# mk312_smt_main_V2.net
KiCad netlist of a schematic drawn in EAGLE
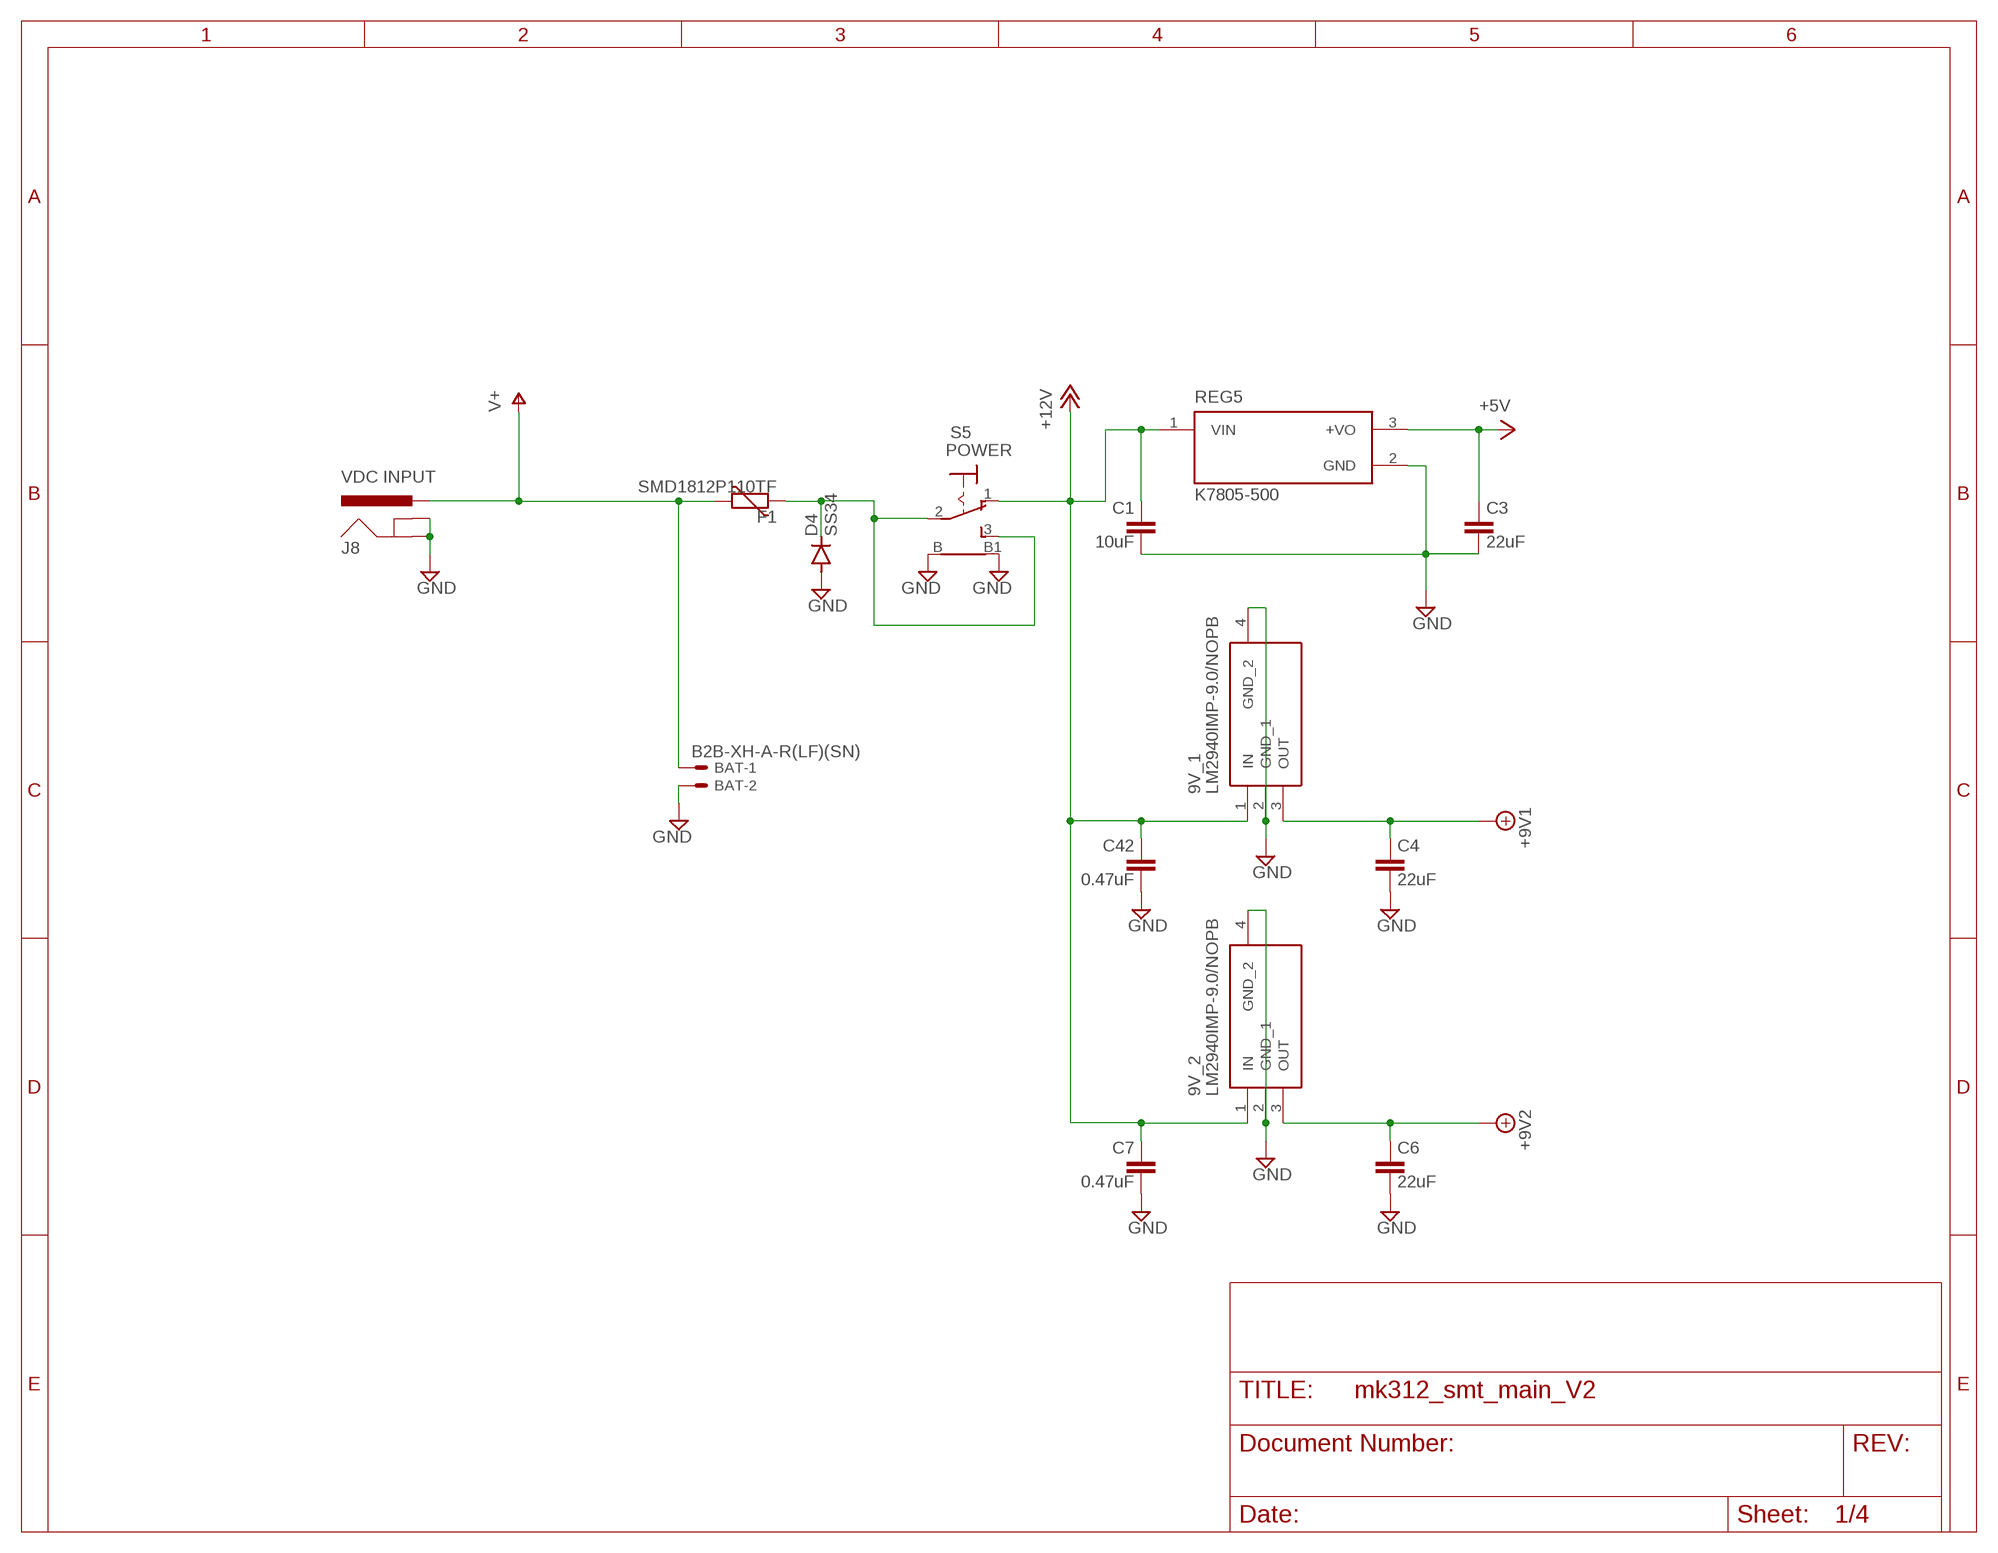
[diagram p0: schematic, sheet 1]
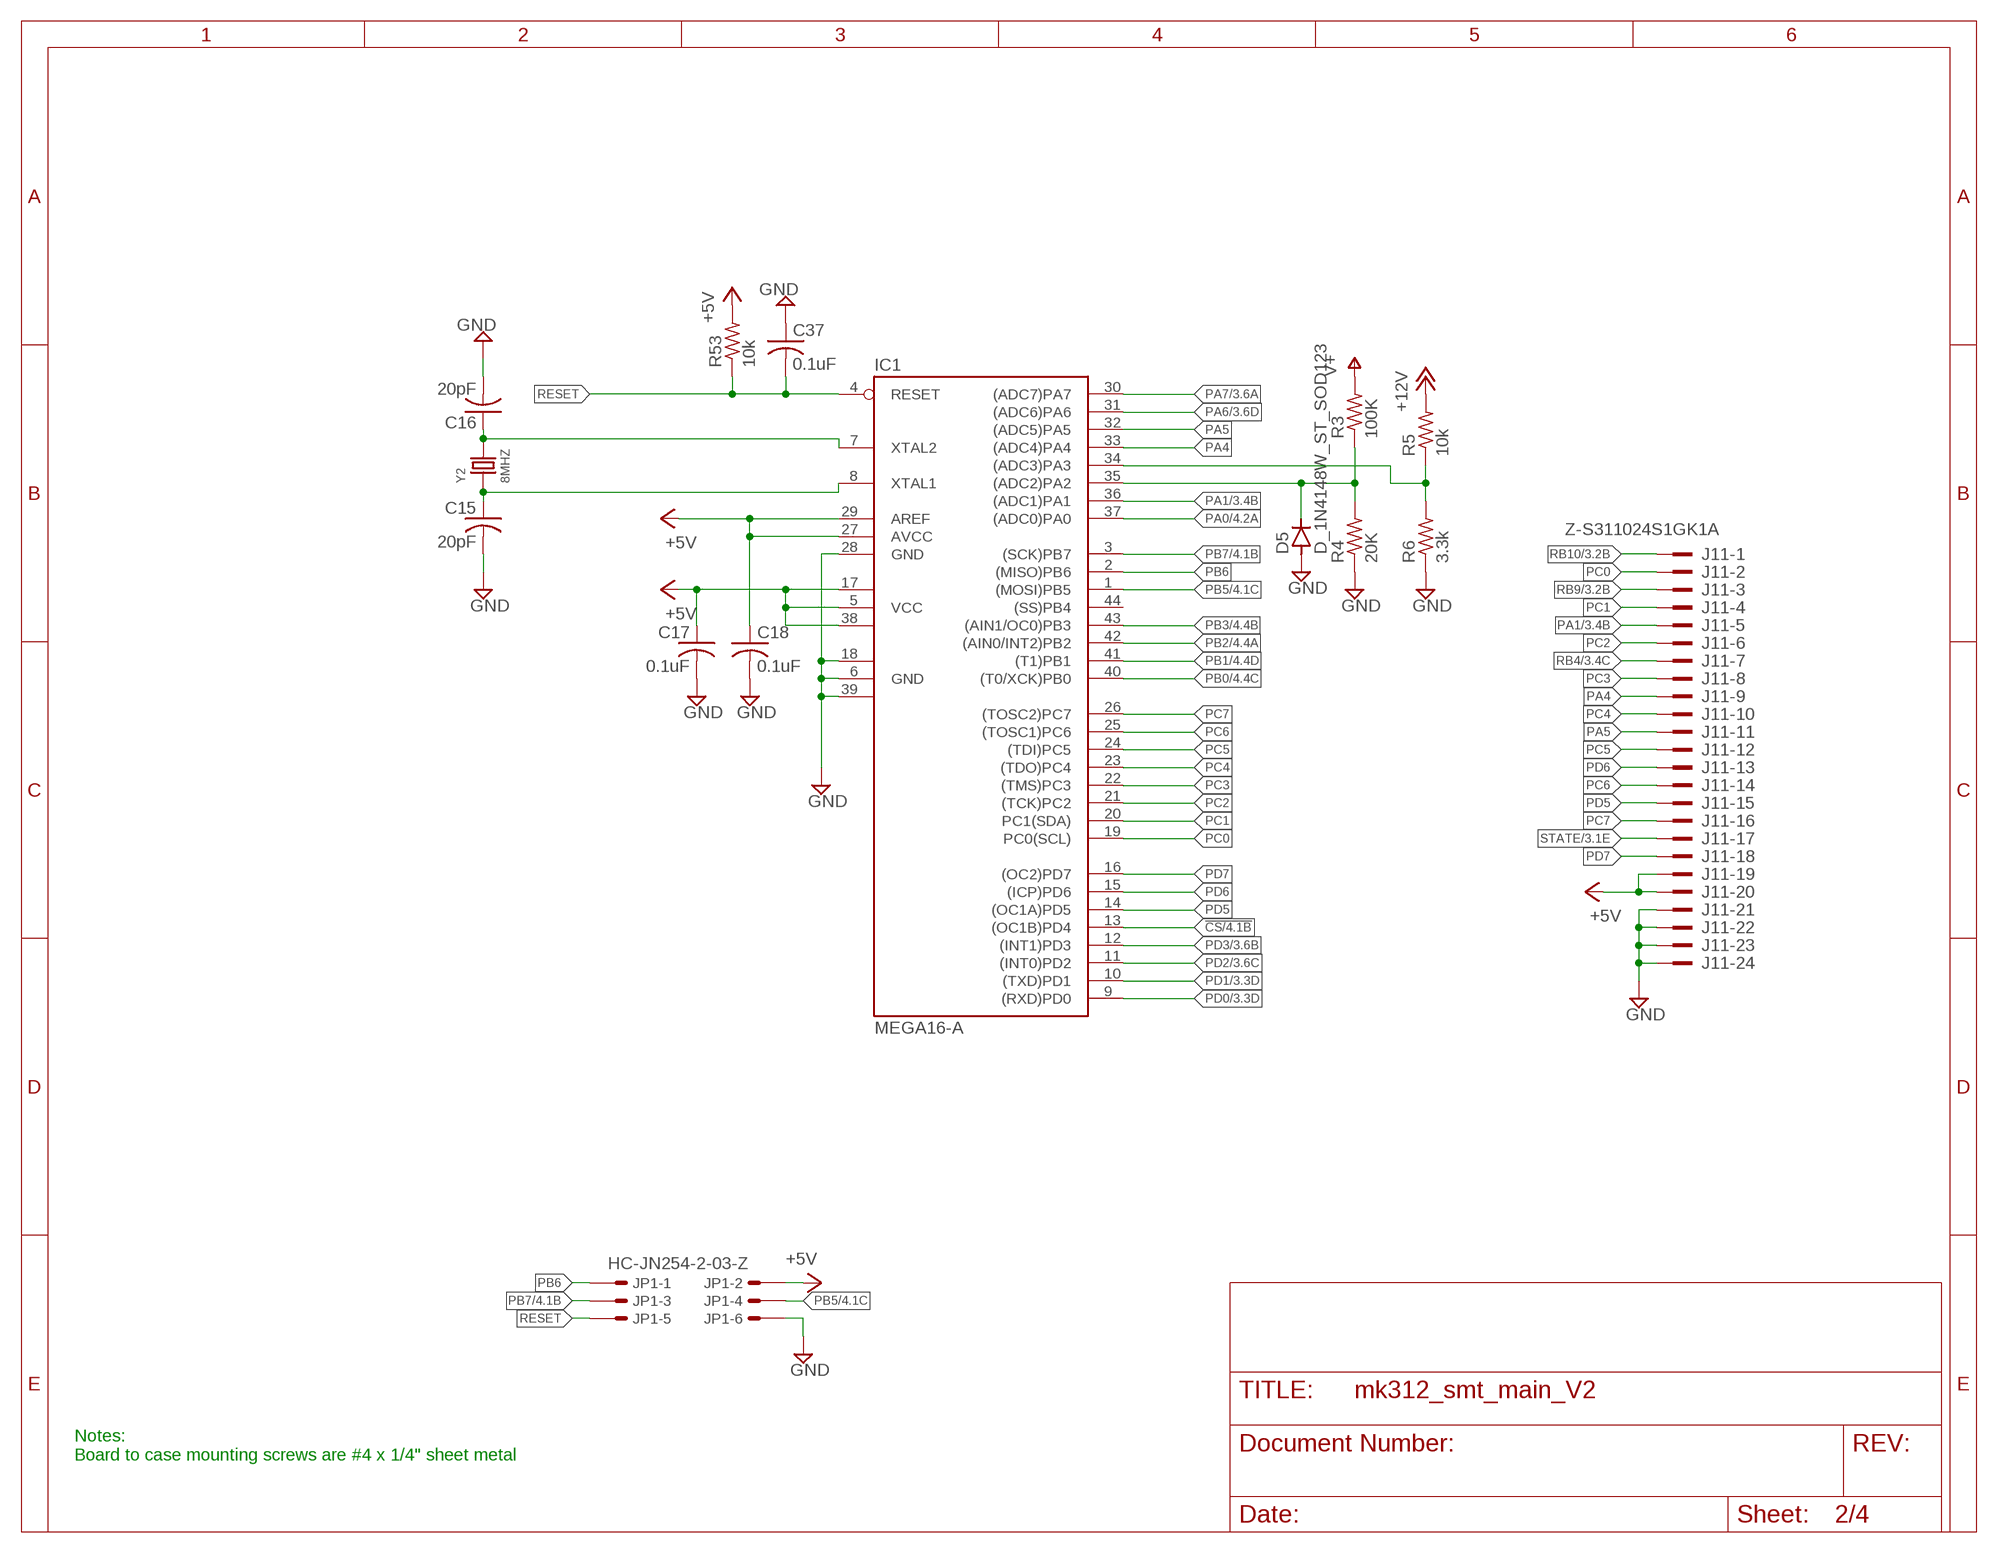
[diagram p1: schematic, sheet 2]
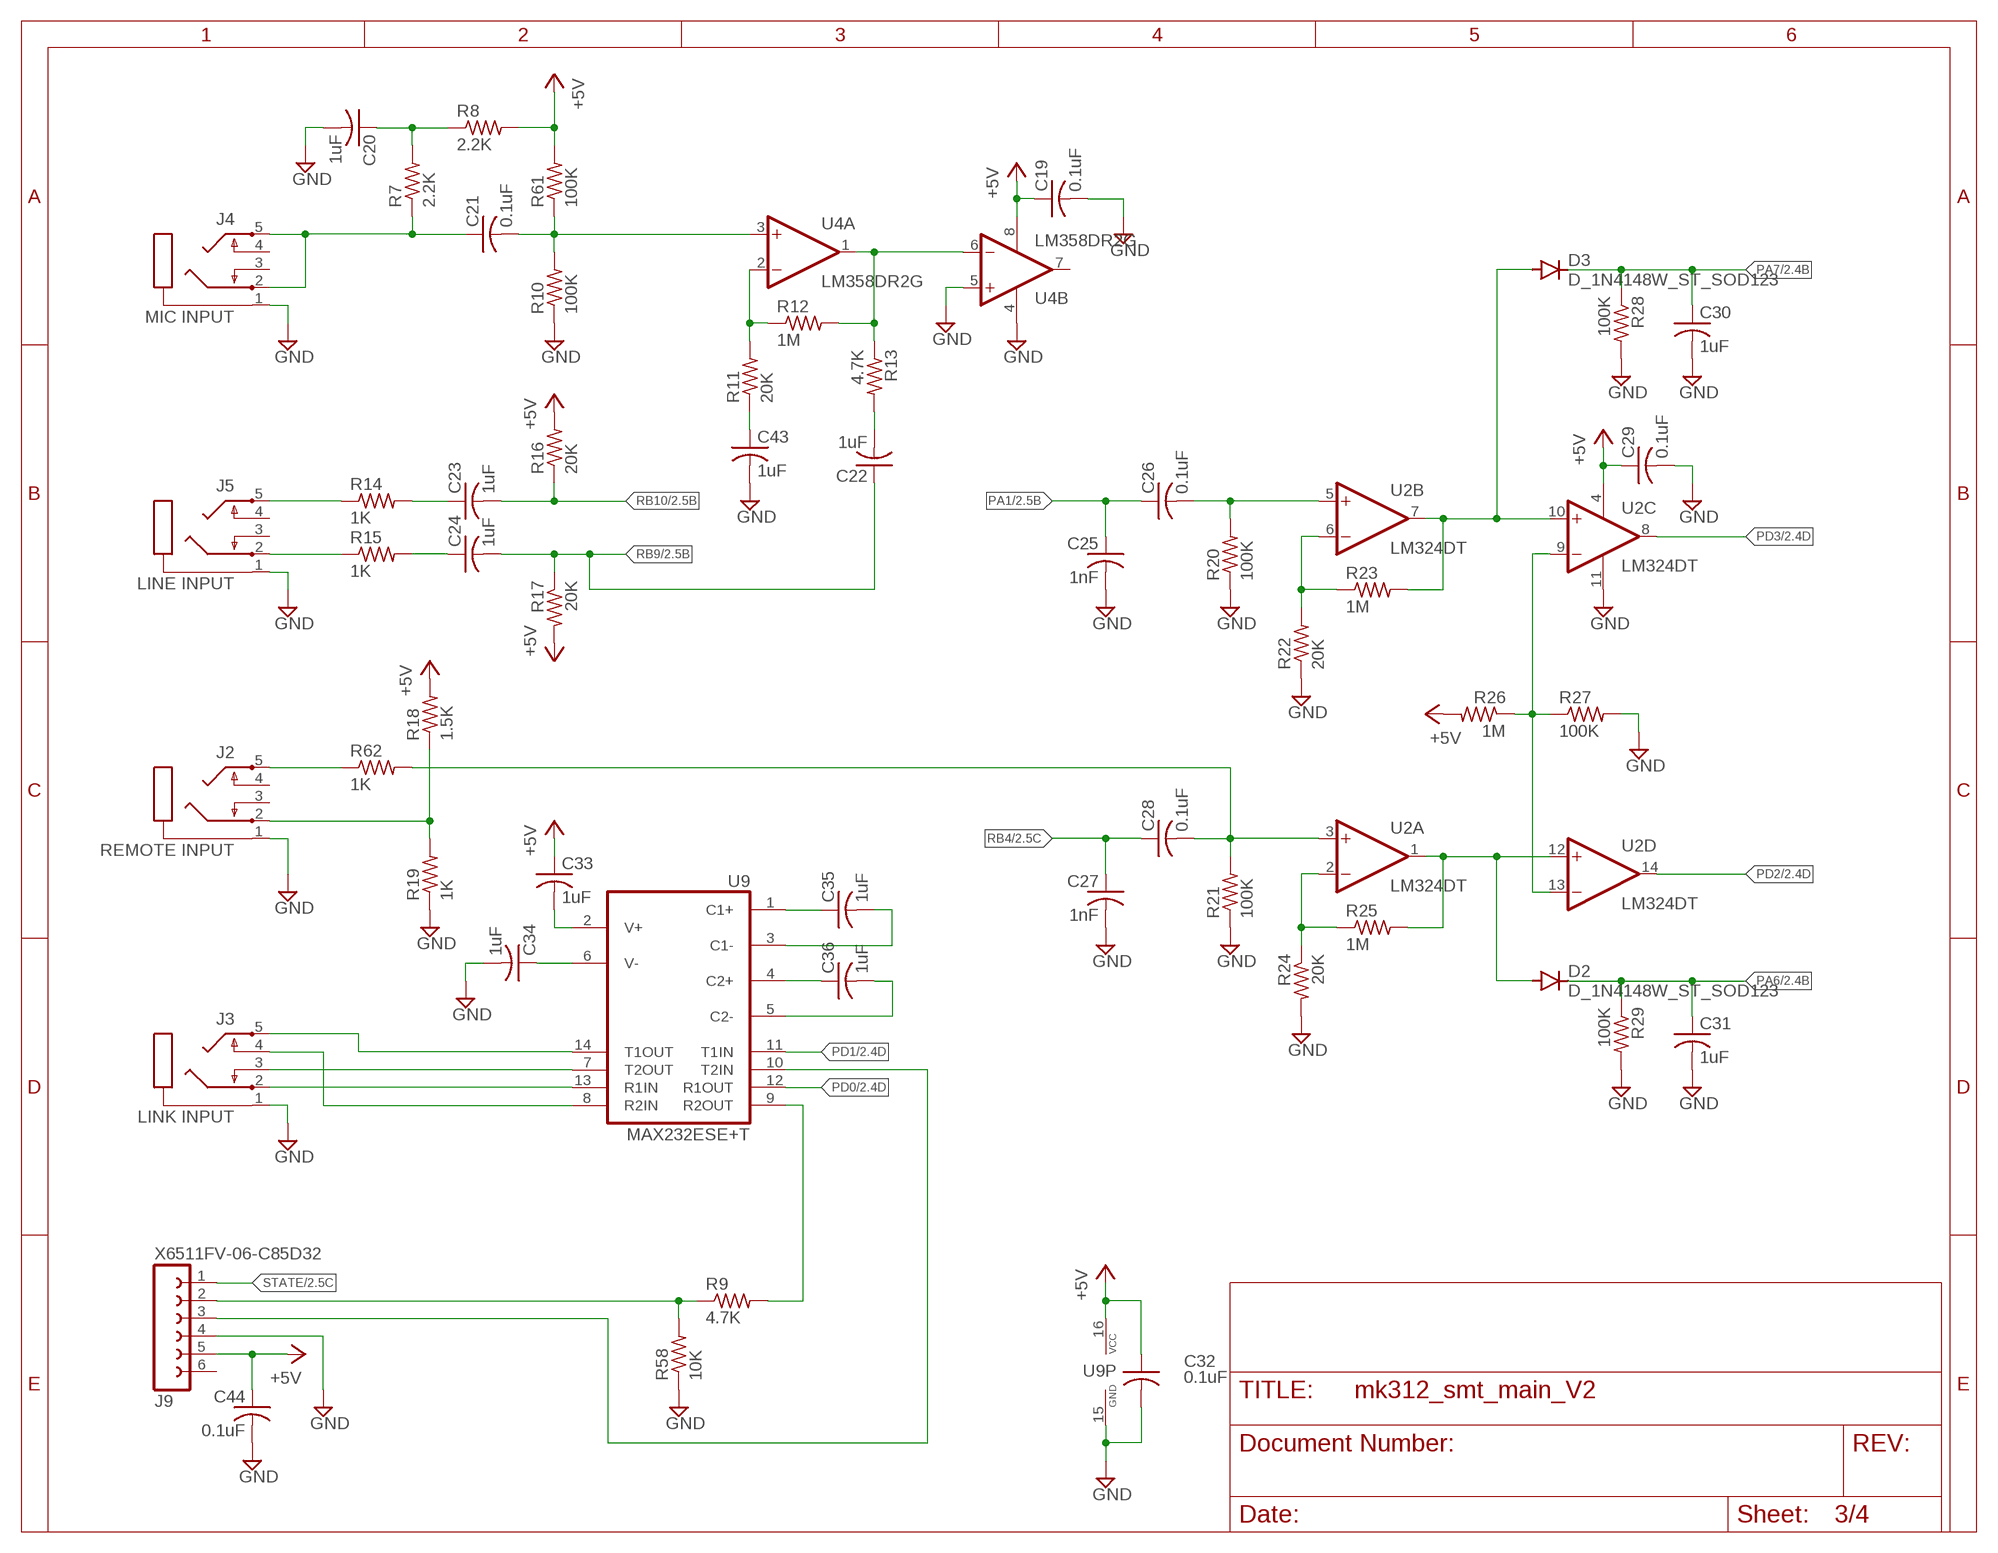
[diagram p2: schematic, sheet 3]
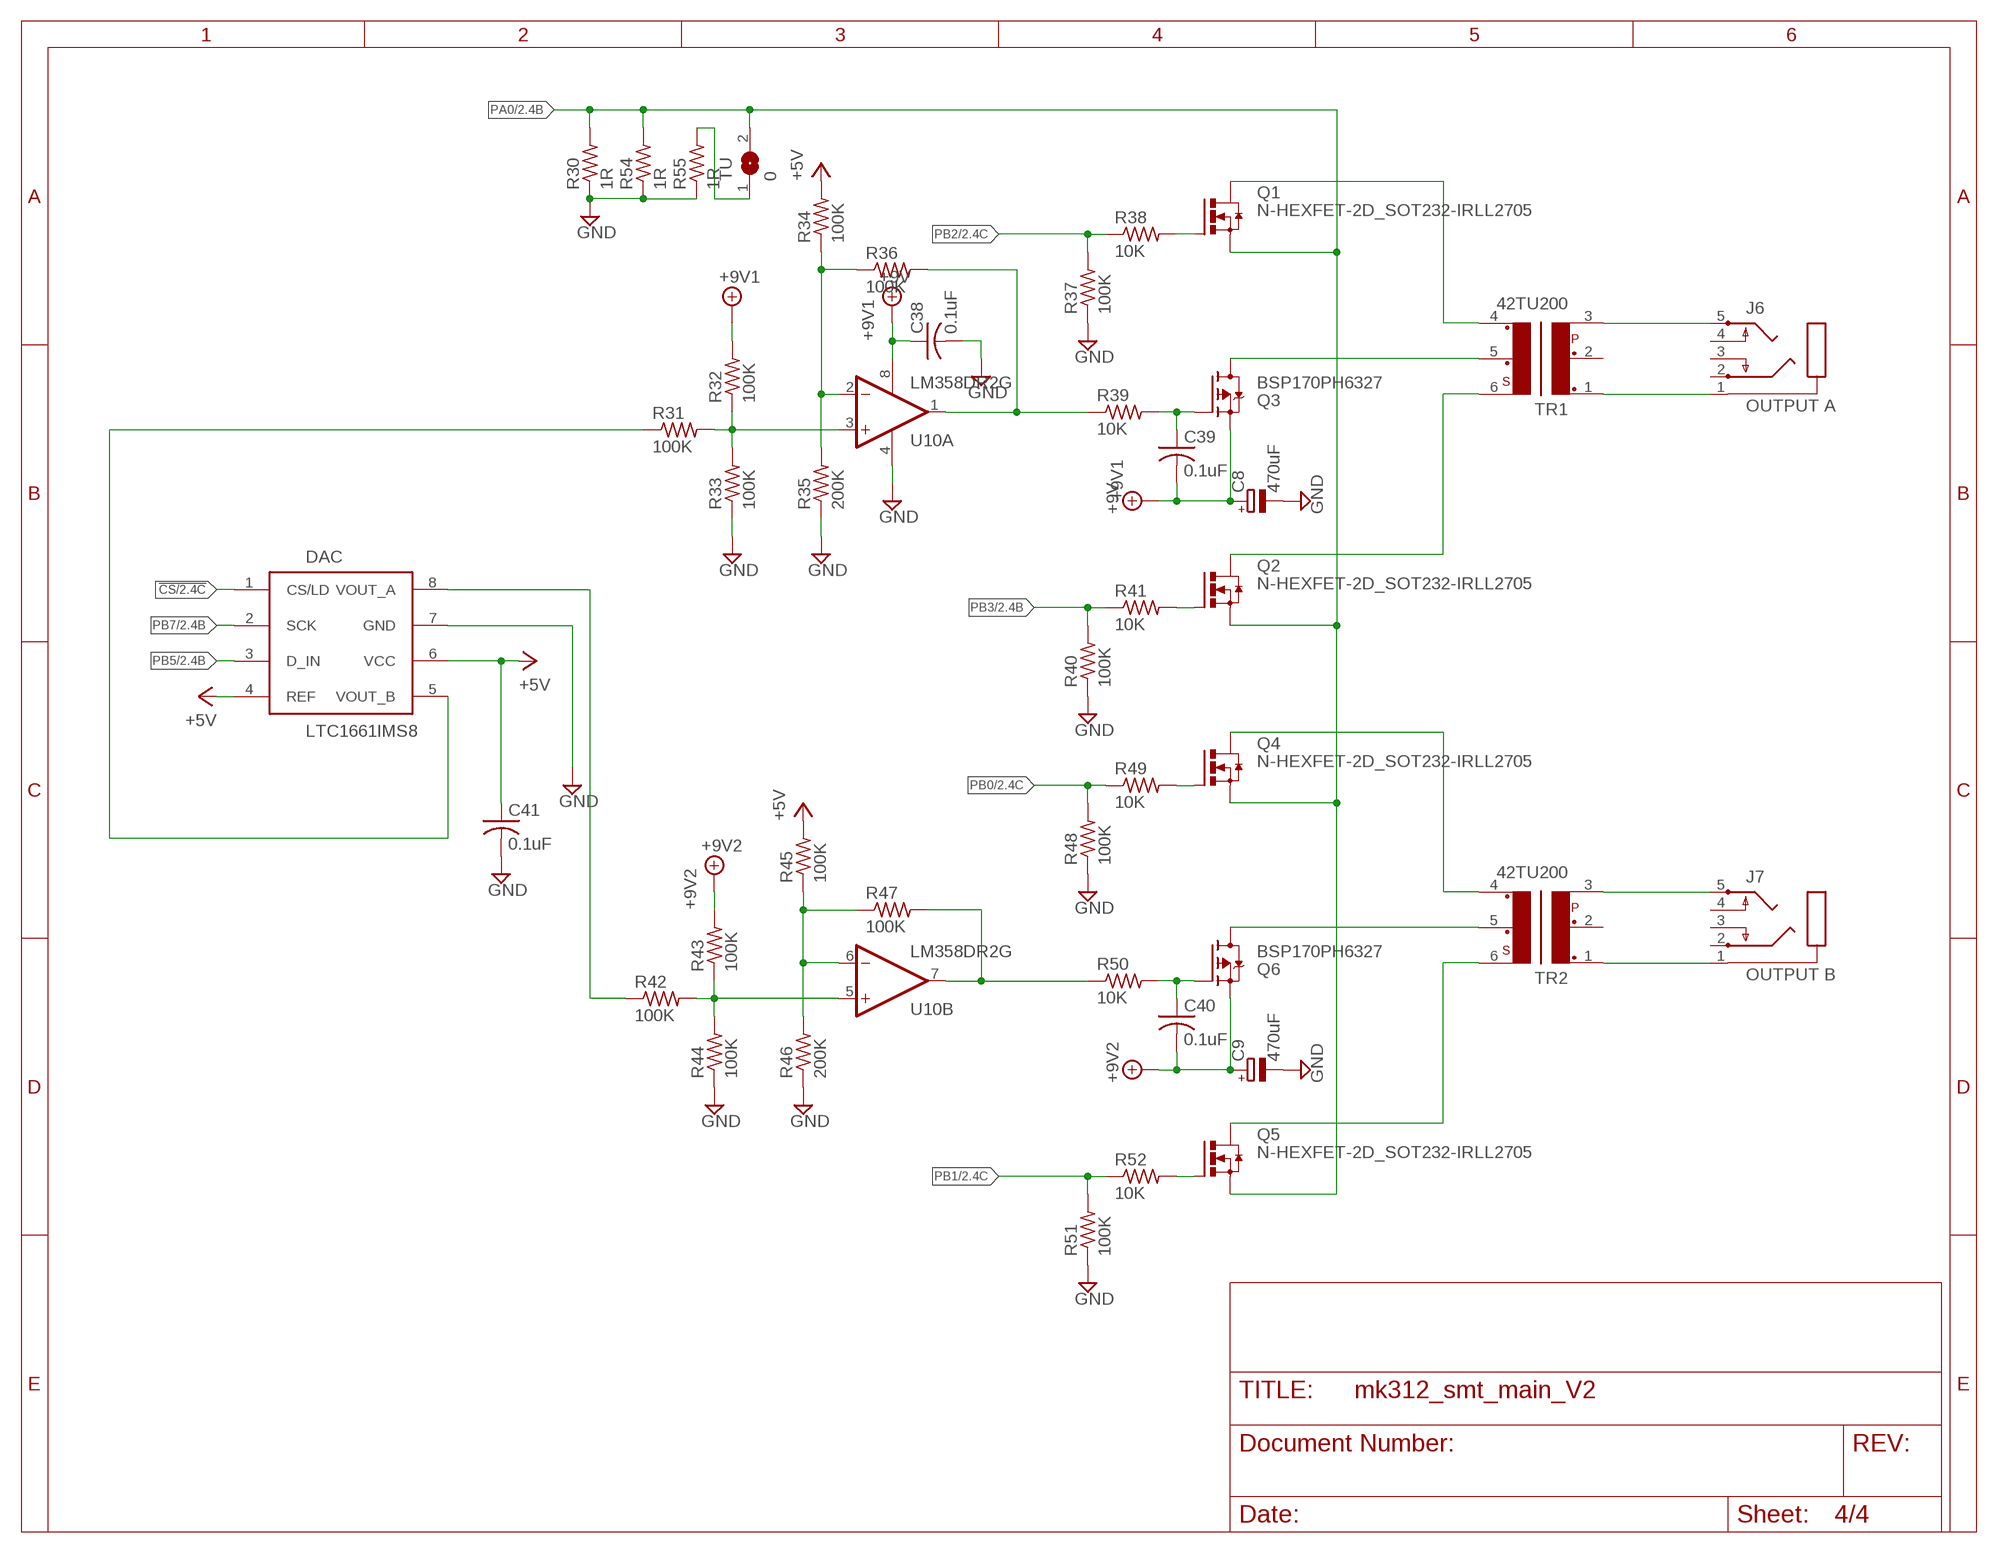
[diagram p3: schematic, sheet 4]

(export (version "E")
  (design (tool "Eeschema 10.0.6"))
  (components
    (comp (ref "C8")
      (value "470uF")
      (footprint "eagle-import:150CLZ-1010")
      (libsource (lib "eagle-import") (part "CPOL-EU150CLZ-1010"))
    )
    (comp (ref "C9")
      (value "470uF")
      (footprint "eagle-import:150CLZ-1010")
      (libsource (lib "eagle-import") (part "CPOL-EU150CLZ-1010"))
    )
    (comp (ref "C38")
      (value "0.1uF")
      (footprint "eagle-import:C0805")
      (libsource (lib "eagle-import") (part "C-USC0805"))
    )
    (comp (ref "C39")
      (value "0.1uF")
      (footprint "eagle-import:C0805")
      (libsource (lib "eagle-import") (part "C-USC0805"))
    )
    (comp (ref "C40")
      (value "0.1uF")
      (footprint "eagle-import:C0805")
      (libsource (lib "eagle-import") (part "C-USC0805"))
    )
    (comp (ref "C41")
      (value "0.1uF")
      (footprint "eagle-import:C0805")
      (libsource (lib "eagle-import") (part "C-USC0805"))
    )
    (comp (ref "DAC")
      (value "LTC1661IMS8")
      (footprint "eagle-import:MSOP8")
      (libsource (lib "eagle-import") (part "LTC1661IMS8"))
    )
    (comp (ref "J6")
      (value "OUTPUT A")
      (footprint "eagle-import:STX3100")
      (libsource (lib "eagle-import") (part "STEREOJACK"))
    )
    (comp (ref "J7")
      (value "OUTPUT B")
      (footprint "eagle-import:STX3100")
      (libsource (lib "eagle-import") (part "STEREOJACK"))
    )
    (comp (ref "Q1")
      (value "N-HEXFET-2D_SOT232-IRLL2705")
      (footprint "eagle-import:SOT223")
      (libsource (lib "eagle-import") (part "N-HEXFET-2D_?-SOT232IRLL2705"))
    )
    (comp (ref "Q2")
      (value "N-HEXFET-2D_SOT232-IRLL2705")
      (footprint "eagle-import:SOT223")
      (libsource (lib "eagle-import") (part "N-HEXFET-2D_?-SOT232IRLL2705"))
    )
    (comp (ref "Q3")
      (value "BSP170PH6327")
      (footprint "eagle-import:SOT230P700X180-4N")
      (libsource (lib "eagle-import") (part "IRFL9014TRPBF"))
    )
    (comp (ref "Q4")
      (value "N-HEXFET-2D_SOT232-IRLL2705")
      (footprint "eagle-import:SOT223")
      (libsource (lib "eagle-import") (part "N-HEXFET-2D_?-SOT232IRLL2705"))
    )
    (comp (ref "Q5")
      (value "N-HEXFET-2D_SOT232-IRLL2705")
      (footprint "eagle-import:SOT223")
      (libsource (lib "eagle-import") (part "N-HEXFET-2D_?-SOT232IRLL2705"))
    )
    (comp (ref "Q6")
      (value "BSP170PH6327")
      (footprint "eagle-import:SOT230P700X180-4N")
      (libsource (lib "eagle-import") (part "IRFL9014TRPBF"))
    )
    (comp (ref "R30")
      (value "1R")
      (footprint "eagle-import:R1206")
      (libsource (lib "eagle-import") (part "R-US_R1206"))
    )
    (comp (ref "R31")
      (value "100K")
      (footprint "eagle-import:R0805")
      (libsource (lib "eagle-import") (part "R-US_R0805"))
    )
    (comp (ref "R32")
      (value "100K")
      (footprint "eagle-import:R0805")
      (libsource (lib "eagle-import") (part "R-US_R0805"))
    )
    (comp (ref "R33")
      (value "100K")
      (footprint "eagle-import:R0805")
      (libsource (lib "eagle-import") (part "R-US_R0805"))
    )
    (comp (ref "R34")
      (value "100K")
      (footprint "eagle-import:R0805")
      (libsource (lib "eagle-import") (part "R-US_R0805"))
    )
    (comp (ref "R35")
      (value "200K")
      (footprint "eagle-import:R0805")
      (libsource (lib "eagle-import") (part "R-US_R0805"))
    )
    (comp (ref "R36")
      (value "100K")
      (footprint "eagle-import:R0805")
      (libsource (lib "eagle-import") (part "R-US_R0805"))
    )
    (comp (ref "R37")
      (value "100K")
      (footprint "eagle-import:R0805")
      (libsource (lib "eagle-import") (part "R-US_R0805"))
    )
    (comp (ref "R38")
      (value "10K")
      (footprint "eagle-import:R0805")
      (libsource (lib "eagle-import") (part "R-US_R0805"))
    )
    (comp (ref "R39")
      (value "10K")
      (footprint "eagle-import:R0805")
      (libsource (lib "eagle-import") (part "R-US_R0805"))
    )
    (comp (ref "R40")
      (value "100K")
      (footprint "eagle-import:R0805")
      (libsource (lib "eagle-import") (part "R-US_R0805"))
    )
    (comp (ref "R41")
      (value "10K")
      (footprint "eagle-import:R0805")
      (libsource (lib "eagle-import") (part "R-US_R0805"))
    )
    (comp (ref "R42")
      (value "100K")
      (footprint "eagle-import:R0805")
      (libsource (lib "eagle-import") (part "R-US_R0805"))
    )
    (comp (ref "R43")
      (value "100K")
      (footprint "eagle-import:R0805")
      (libsource (lib "eagle-import") (part "R-US_R0805"))
    )
    (comp (ref "R44")
      (value "100K")
      (footprint "eagle-import:R0805")
      (libsource (lib "eagle-import") (part "R-US_R0805"))
    )
    (comp (ref "R45")
      (value "100K")
      (footprint "eagle-import:R0805")
      (libsource (lib "eagle-import") (part "R-US_R0805"))
    )
    (comp (ref "R46")
      (value "200K")
      (footprint "eagle-import:R0805")
      (libsource (lib "eagle-import") (part "R-US_R0805"))
    )
    (comp (ref "R47")
      (value "100K")
      (footprint "eagle-import:R0805")
      (libsource (lib "eagle-import") (part "R-US_R0805"))
    )
    (comp (ref "R48")
      (value "100K")
      (footprint "eagle-import:R0805")
      (libsource (lib "eagle-import") (part "R-US_R0805"))
    )
    (comp (ref "R49")
      (value "10K")
      (footprint "eagle-import:R0805")
      (libsource (lib "eagle-import") (part "R-US_R0805"))
    )
    (comp (ref "R50")
      (value "10K")
      (footprint "eagle-import:R0805")
      (libsource (lib "eagle-import") (part "R-US_R0805"))
    )
    (comp (ref "R51")
      (value "100K")
      (footprint "eagle-import:R0805")
      (libsource (lib "eagle-import") (part "R-US_R0805"))
    )
    (comp (ref "R52")
      (value "10K")
      (footprint "eagle-import:R0805")
      (libsource (lib "eagle-import") (part "R-US_R0805"))
    )
    (comp (ref "R54")
      (value "1R")
      (footprint "eagle-import:R1206")
      (libsource (lib "eagle-import") (part "R-US_R1206"))
    )
    (comp (ref "R55")
      (value "1R")
      (footprint "eagle-import:R1206")
      (libsource (lib "eagle-import") (part "R-US_R1206"))
    )
    (comp (ref "TR1")
      (value "42TU200")
      (footprint "eagle-import:42TL")
      (libsource (lib "eagle-import") (part "42T?42TU"))
    )
    (comp (ref "TR2")
      (value "42TU200")
      (footprint "eagle-import:42TL")
      (libsource (lib "eagle-import") (part "42T?42TU"))
    )
    (comp (ref "TU") (value "0") (footprint "eagle-import:SJ") (libsource (lib "eagle-import") (part "SJ")))
    (comp (ref "U10")
      (value "LM358DR2G")
      (footprint "eagle-import:SO08")
      (libsource (lib "eagle-import") (part "LM358D"))
    )
    (comp (ref "9V_1")
      (value "LM2940IMP-9.0/NOPB")
      (footprint "eagle-import:SOT230P700X180-4N")
      (fields (field (name "MOUSER_PART_NUMBER") "926-LM2940IMP90NOPB"))
      (libsource (lib "eagle-import") (part "LM2940IMP-9.0_NOPB"))
    )
    (comp (ref "9V_2")
      (value "LM2940IMP-9.0/NOPB")
      (footprint "eagle-import:SOT230P700X180-4N")
      (fields (field (name "MOUSER_PART_NUMBER") "926-LM2940IMP90NOPB"))
      (libsource (lib "eagle-import") (part "LM2940IMP-9.0_NOPB"))
    )
    (comp (ref "BAT")
      (value "B2B-XH-A-R(LF)(SN)")
      (footprint "eagle-import:JST-XH-02-PACKAGE-LONG-PAD")
      (libsource (lib "eagle-import") (part "JST-XH-02-PIN-LONG-PAD"))
    )
    (comp (ref "C1")
      (value "10uF")
      (footprint "eagle-import:C0805")
      (libsource (lib "eagle-import") (part "C-EUC0805"))
    )
    (comp (ref "C3")
      (value "22uF")
      (footprint "eagle-import:C1206")
      (libsource (lib "eagle-import") (part "C-EUC1206"))
    )
    (comp (ref "C4")
      (value "22uF")
      (footprint "eagle-import:C1206")
      (libsource (lib "eagle-import") (part "C-EUC1206"))
    )
    (comp (ref "C6")
      (value "22uF")
      (footprint "eagle-import:C1206")
      (libsource (lib "eagle-import") (part "C-EUC1206"))
    )
    (comp (ref "C7")
      (value "0.47uF")
      (footprint "eagle-import:C0805")
      (libsource (lib "eagle-import") (part "C-EUC0805"))
    )
    (comp (ref "C42")
      (value "0.47uF")
      (footprint "eagle-import:C0805")
      (libsource (lib "eagle-import") (part "C-EUC0805"))
    )
    (comp (ref "D4")
      (value "SS34")
      (footprint "eagle-import:SMA")
      (libsource (lib "eagle-import") (part "S1M"))
    )
    (comp (ref "F1")
      (value "SMD1812P110TF")
      (footprint "eagle-import:CT_CN1812")
      (libsource (lib "eagle-import") (part "VARISTORCN1812"))
    )
    (comp (ref "J8")
      (value "VDC INPUT")
      (footprint "eagle-import:POWER_JACK_SLOT")
      (libsource (lib "eagle-import") (part "POWER_JACKSLT"))
    )
    (comp (ref "REG5")
      (value "K7805-500")
      (footprint "eagle-import:CONV_K7809M-1000R3")
      (fields (field (name "MF") "Mornsun America, LLC") (field (name "MP") "K7809M-1000R3"))
      (libsource (lib "eagle-import") (part "K7809M-1000R3"))
    )
    (comp (ref "S5")
      (value "POWER")
      (footprint "eagle-import:LPV-1")
      (libsource (lib "eagle-import") (part "LPV-1"))
    )
    (comp (ref "C15")
      (value "20pF")
      (footprint "eagle-import:C0603")
      (libsource (lib "eagle-import") (part "C-USC0603"))
    )
    (comp (ref "C16")
      (value "20pF")
      (footprint "eagle-import:C0603")
      (libsource (lib "eagle-import") (part "C-USC0603"))
    )
    (comp (ref "C17")
      (value "0.1uF")
      (footprint "eagle-import:C0805")
      (libsource (lib "eagle-import") (part "C-USC0805"))
    )
    (comp (ref "C18")
      (value "0.1uF")
      (footprint "eagle-import:C0805")
      (libsource (lib "eagle-import") (part "C-USC0805"))
    )
    (comp (ref "C37")
      (value "0.1uF")
      (footprint "eagle-import:C0805")
      (libsource (lib "eagle-import") (part "rcl_334_C-USC0805"))
    )
    (comp (ref "D5")
      (value "D_1N4148W_ST_SOD123")
      (footprint "eagle-import:SOD123")
      (fields (field (name "LCSC_PART") "C81598"))
      (libsource (lib "eagle-import") (part "D__SOD1231N4148W_ST"))
    )
    (comp (ref "IC1")
      (value "MEGA16-A")
      (footprint "eagle-import:TQFP44")
      (fields (field (name "MPN") "ATMEGA16-16AU"))
      (libsource (lib "eagle-import") (part "MEGA16-A"))
    )
    (comp (ref "J11")
      (value "Z-S311024S1GK1A")
      (footprint "eagle-import:PAK100_2500-24")
      (libsource (lib "eagle-import") (part "2524-"))
    )
    (comp (ref "JP1")
      (value "HC-JN254-2-03-Z")
      (footprint "eagle-import:057-006-1")
      (libsource (lib "eagle-import") (part "057-006-1"))
    )
    (comp (ref "R3")
      (value "100K")
      (footprint "eagle-import:R0805")
      (libsource (lib "eagle-import") (part "R-US_R0805"))
    )
    (comp (ref "R4")
      (value "20K")
      (footprint "eagle-import:R0805")
      (libsource (lib "eagle-import") (part "R-US_R0805"))
    )
    (comp (ref "R5")
      (value "10k")
      (footprint "eagle-import:R0805")
      (libsource (lib "eagle-import") (part "R-US_R0805"))
    )
    (comp (ref "R6")
      (value "3.3k")
      (footprint "eagle-import:R0805")
      (libsource (lib "eagle-import") (part "R-US_R0805"))
    )
    (comp (ref "R53")
      (value "10k")
      (footprint "eagle-import:R0805")
      (libsource (lib "eagle-import") (part "rcl_334_R-US_R0805"))
    )
    (comp (ref "Y2")
      (value "8MHZ")
      (footprint "eagle-import:X2-SMD-5.0X3.2X1.3MM")
      (fields (field (name "MPN") "5032/2P"))
      (libsource (lib "eagle-import") (part "SMD-CRYSTAL-8MHZ-20PF-20PPM(2P-5.0X3.2MM)"))
    )
    (comp (ref "C19")
      (value "0.1uF")
      (footprint "eagle-import:C0805")
      (libsource (lib "eagle-import") (part "C-USC0805"))
    )
    (comp (ref "C20")
      (value "1uF")
      (footprint "eagle-import:C0805")
      (libsource (lib "eagle-import") (part "C-USC0805"))
    )
    (comp (ref "C21")
      (value "0.1uF")
      (footprint "eagle-import:C0805")
      (libsource (lib "eagle-import") (part "C-USC0805"))
    )
    (comp (ref "C22")
      (value "1uF")
      (footprint "eagle-import:C0805")
      (libsource (lib "eagle-import") (part "C-USC0805"))
    )
    (comp (ref "C23")
      (value "1uF")
      (footprint "eagle-import:C0805")
      (libsource (lib "eagle-import") (part "C-USC0805"))
    )
    (comp (ref "C24")
      (value "1uF")
      (footprint "eagle-import:C0805")
      (libsource (lib "eagle-import") (part "C-USC0805"))
    )
    (comp (ref "C25")
      (value "1nF")
      (footprint "eagle-import:C0805")
      (libsource (lib "eagle-import") (part "C-USC0805"))
    )
    (comp (ref "C26")
      (value "0.1uF")
      (footprint "eagle-import:C0805")
      (libsource (lib "eagle-import") (part "C-USC0805"))
    )
    (comp (ref "C27")
      (value "1nF")
      (footprint "eagle-import:C0805")
      (libsource (lib "eagle-import") (part "C-USC0805"))
    )
    (comp (ref "C28")
      (value "0.1uF")
      (footprint "eagle-import:C0805")
      (libsource (lib "eagle-import") (part "C-USC0805"))
    )
    (comp (ref "C29")
      (value "0.1uF")
      (footprint "eagle-import:C0805")
      (libsource (lib "eagle-import") (part "C-USC0805"))
    )
    (comp (ref "C30")
      (value "1uF")
      (footprint "eagle-import:C0805")
      (libsource (lib "eagle-import") (part "C-USC0805"))
    )
    (comp (ref "C31")
      (value "1uF")
      (footprint "eagle-import:C0805")
      (libsource (lib "eagle-import") (part "C-USC0805"))
    )
    (comp (ref "C32")
      (value "0.1uF")
      (footprint "eagle-import:C0805")
      (libsource (lib "eagle-import") (part "C-USC0805"))
    )
    (comp (ref "C33")
      (value "1uF")
      (footprint "eagle-import:C0805")
      (libsource (lib "eagle-import") (part "C-USC0805"))
    )
    (comp (ref "C34")
      (value "1uF")
      (footprint "eagle-import:C0805")
      (libsource (lib "eagle-import") (part "C-USC0805"))
    )
    (comp (ref "C35")
      (value "1uF")
      (footprint "eagle-import:C0805")
      (libsource (lib "eagle-import") (part "C-USC0805"))
    )
    (comp (ref "C36")
      (value "1uF")
      (footprint "eagle-import:C0805")
      (libsource (lib "eagle-import") (part "C-USC0805"))
    )
    (comp (ref "C43")
      (value "1uF")
      (footprint "eagle-import:C0805")
      (libsource (lib "eagle-import") (part "C-USC0805"))
    )
    (comp (ref "C44")
      (value "0.1uF")
      (footprint "eagle-import:C0805")
      (libsource (lib "eagle-import") (part "C-USC0805"))
    )
    (comp (ref "D2")
      (value "D_1N4148W_ST_SOD123")
      (footprint "eagle-import:SOD123")
      (fields (field (name "LCSC_PART") "C81598"))
      (libsource (lib "eagle-import") (part "D__SOD1231N4148W_ST"))
    )
    (comp (ref "D3")
      (value "D_1N4148W_ST_SOD123")
      (footprint "eagle-import:SOD123")
      (fields (field (name "LCSC_PART") "C81598"))
      (libsource (lib "eagle-import") (part "D__SOD1231N4148W_ST"))
    )
    (comp (ref "J2")
      (value "REMOTE INPUT")
      (footprint "eagle-import:STX3100")
      (libsource (lib "eagle-import") (part "STEREOJACK"))
    )
    (comp (ref "J3")
      (value "LINK INPUT")
      (footprint "eagle-import:STX3100")
      (libsource (lib "eagle-import") (part "STEREOJACK"))
    )
    (comp (ref "J4")
      (value "MIC INPUT")
      (footprint "eagle-import:STX3100")
      (libsource (lib "eagle-import") (part "STEREOJACK"))
    )
    (comp (ref "J5")
      (value "LINE INPUT")
      (footprint "eagle-import:STX3100")
      (libsource (lib "eagle-import") (part "STEREOJACK"))
    )
    (comp (ref "J9")
      (value "X6511FV-06-C85D32")
      (footprint "eagle-import:FE06")
      (libsource (lib "eagle-import") (part "FE06-1"))
    )
    (comp (ref "R7")
      (value "2.2K")
      (footprint "eagle-import:R0805")
      (libsource (lib "eagle-import") (part "R-US_R0805"))
    )
    (comp (ref "R8")
      (value "2.2K")
      (footprint "eagle-import:R0805")
      (libsource (lib "eagle-import") (part "R-US_R0805"))
    )
    (comp (ref "R9")
      (value "4.7K")
      (footprint "eagle-import:R0805")
      (libsource (lib "eagle-import") (part "R-US_R0805"))
    )
    (comp (ref "R10")
      (value "100K")
      (footprint "eagle-import:R0805")
      (libsource (lib "eagle-import") (part "R-US_R0805"))
    )
    (comp (ref "R11")
      (value "20K")
      (footprint "eagle-import:R0805")
      (libsource (lib "eagle-import") (part "R-US_R0805"))
    )
    (comp (ref "R12")
      (value "1M")
      (footprint "eagle-import:R0805")
      (libsource (lib "eagle-import") (part "R-US_R0805"))
    )
    (comp (ref "R13")
      (value "4.7K")
      (footprint "eagle-import:R0805")
      (libsource (lib "eagle-import") (part "R-US_R0805"))
    )
    (comp (ref "R14")
      (value "1K")
      (footprint "eagle-import:R0805")
      (libsource (lib "eagle-import") (part "R-US_R0805"))
    )
    (comp (ref "R15")
      (value "1K")
      (footprint "eagle-import:R0805")
      (libsource (lib "eagle-import") (part "R-US_R0805"))
    )
    (comp (ref "R16")
      (value "20K")
      (footprint "eagle-import:R0805")
      (libsource (lib "eagle-import") (part "R-US_R0805"))
    )
    (comp (ref "R17")
      (value "20K")
      (footprint "eagle-import:R0805")
      (libsource (lib "eagle-import") (part "R-US_R0805"))
    )
    (comp (ref "R18")
      (value "1.5K")
      (footprint "eagle-import:R0805")
      (libsource (lib "eagle-import") (part "R-US_R0805"))
    )
    (comp (ref "R19")
      (value "1K")
      (footprint "eagle-import:R0805")
      (libsource (lib "eagle-import") (part "R-US_R0805"))
    )
    (comp (ref "R20")
      (value "100K")
      (footprint "eagle-import:R0805")
      (libsource (lib "eagle-import") (part "R-US_R0805"))
    )
    (comp (ref "R21")
      (value "100K")
      (footprint "eagle-import:R0805")
      (libsource (lib "eagle-import") (part "R-US_R0805"))
    )
    (comp (ref "R22")
      (value "20K")
      (footprint "eagle-import:R0805")
      (libsource (lib "eagle-import") (part "R-US_R0805"))
    )
    (comp (ref "R23")
      (value "1M")
      (footprint "eagle-import:R0805")
      (libsource (lib "eagle-import") (part "R-US_R0805"))
    )
    (comp (ref "R24")
      (value "20K")
      (footprint "eagle-import:R0805")
      (libsource (lib "eagle-import") (part "R-US_R0805"))
    )
    (comp (ref "R25")
      (value "1M")
      (footprint "eagle-import:R0805")
      (libsource (lib "eagle-import") (part "R-US_R0805"))
    )
    (comp (ref "R26")
      (value "1M")
      (footprint "eagle-import:R0805")
      (libsource (lib "eagle-import") (part "R-US_R0805"))
    )
    (comp (ref "R27")
      (value "100K")
      (footprint "eagle-import:R0805")
      (libsource (lib "eagle-import") (part "R-US_R0805"))
    )
    (comp (ref "R28")
      (value "100K")
      (footprint "eagle-import:R0805")
      (libsource (lib "eagle-import") (part "R-US_R0805"))
    )
    (comp (ref "R29")
      (value "100K")
      (footprint "eagle-import:R0805")
      (libsource (lib "eagle-import") (part "R-US_R0805"))
    )
    (comp (ref "R58")
      (value "10K")
      (footprint "eagle-import:R0805")
      (libsource (lib "eagle-import") (part "R-US_R0805"))
    )
    (comp (ref "R61")
      (value "100K")
      (footprint "eagle-import:R0805")
      (libsource (lib "eagle-import") (part "R-US_R0805"))
    )
    (comp (ref "R62")
      (value "1K")
      (footprint "eagle-import:R0805")
      (libsource (lib "eagle-import") (part "R-US_R0805"))
    )
    (comp (ref "U2")
      (value "LM324DT")
      (footprint "eagle-import:SO14")
      (libsource (lib "eagle-import") (part "LM324D"))
    )
    (comp (ref "U4")
      (value "LM358DR2G")
      (footprint "eagle-import:SO08")
      (libsource (lib "eagle-import") (part "LM358D"))
    )
    (comp (ref "U9")
      (value "MAX232ESE+T")
      (footprint "eagle-import:SOP-16")
      (libsource (lib "eagle-import") (part "MAX232ECWESOP16"))
    )
  )
  (nets
    (net (code "1") (name "+5V") (class "Default")
      (node (ref "C17") (pin "1") (pinfunction "1_1") (pintype "passive"))
      (node (ref "C18") (pin "1") (pinfunction "1_1") (pintype "passive"))
      (node (ref "C19") (pin "1") (pinfunction "1_1") (pintype "passive"))
      (node (ref "C29") (pin "1") (pinfunction "1_1") (pintype "passive"))
      (node (ref "C3") (pin "1") (pinfunction "1_1") (pintype "passive"))
      (node (ref "C32") (pin "1") (pinfunction "1_1") (pintype "passive"))
      (node (ref "C33") (pin "1") (pinfunction "1_1") (pintype "passive"))
      (node (ref "C41") (pin "1") (pinfunction "1_1") (pintype "passive"))
      (node (ref "C44") (pin "1") (pinfunction "1_1") (pintype "passive"))
      (node (ref "DAC") (pin "4") (pinfunction "REF_4") (pintype "input"))
      (node (ref "DAC") (pin "6") (pinfunction "VCC_6") (pintype "power_in"))
      (node (ref "IC1") (pin "17") (pinfunction "VCC1_17") (pintype "power_in"))
      (node (ref "IC1") (pin "27") (pinfunction "AVCC_27") (pintype "power_in"))
      (node (ref "IC1") (pin "29") (pinfunction "AREF_29") (pintype "passive"))
      (node (ref "IC1") (pin "38") (pinfunction "VCC2_38") (pintype "power_in"))
      (node (ref "IC1") (pin "5") (pinfunction "VCC_5") (pintype "power_in"))
      (node (ref "J11") (pin "19") (pinfunction "KL_19") (pintype "passive"))
      (node (ref "J11") (pin "20") (pinfunction "KL_20") (pintype "passive"))
      (node (ref "J9") (pin "5") (pinfunction "5_5") (pintype "passive"))
      (node (ref "JP1") (pin "2") (pinfunction "S_2") (pintype "passive"))
      (node (ref "R16") (pin "2") (pinfunction "2_2") (pintype "passive"))
      (node (ref "R17") (pin "2") (pinfunction "2_2") (pintype "passive"))
      (node (ref "R18") (pin "2") (pinfunction "2_2") (pintype "passive"))
      (node (ref "R26") (pin "2") (pinfunction "2_2") (pintype "passive"))
      (node (ref "R34") (pin "2") (pinfunction "2_2") (pintype "passive"))
      (node (ref "R45") (pin "2") (pinfunction "2_2") (pintype "passive"))
      (node (ref "R53") (pin "2") (pinfunction "2_2") (pintype "passive"))
      (node (ref "R61") (pin "2") (pinfunction "2_2") (pintype "passive"))
      (node (ref "R8") (pin "2") (pinfunction "2_2") (pintype "passive"))
      (node (ref "REG5") (pin "3") (pinfunction "+VO_3") (pintype "output"))
      (node (ref "U2") (pin "4") (pinfunction "V+_4") (pintype "power_in"))
      (node (ref "U4") (pin "8") (pinfunction "V+_8") (pintype "power_in"))
      (node (ref "U9") (pin "16") (pinfunction "VCC_16") (pintype "power_in"))
    )
    (net (code "2") (name "+9V1") (class "Default")
      (node (ref "9V_1") (pin "3") (pinfunction "OUT_3") (pintype "power_in"))
      (node (ref "C38") (pin "1") (pinfunction "1_1") (pintype "passive"))
      (node (ref "C39") (pin "2") (pinfunction "2_2") (pintype "passive"))
      (node (ref "C4") (pin "1") (pinfunction "1_1") (pintype "passive"))
      (node (ref "C8") (pin "+") (pinfunction "+_+") (pintype "passive"))
      (node (ref "Q3") (pin "3") (pinfunction "S_3") (pintype "passive"))
      (node (ref "R32") (pin "2") (pinfunction "2_2") (pintype "passive"))
      (node (ref "U10") (pin "8") (pinfunction "V+_8") (pintype "power_in"))
    )
    (net (code "3") (name "+9V2") (class "Default")
      (node (ref "9V_2") (pin "3") (pinfunction "OUT_3") (pintype "power_in"))
      (node (ref "C40") (pin "2") (pinfunction "2_2") (pintype "passive"))
      (node (ref "C6") (pin "1") (pinfunction "1_1") (pintype "passive"))
      (node (ref "C9") (pin "+") (pinfunction "+_+") (pintype "passive"))
      (node (ref "Q6") (pin "3") (pinfunction "S_3") (pintype "passive"))
      (node (ref "R43") (pin "2") (pinfunction "2_2") (pintype "passive"))
    )
    (net (code "4") (name "+12V") (class "Default")
      (node (ref "9V_1") (pin "1") (pinfunction "IN_1") (pintype "input"))
      (node (ref "9V_2") (pin "1") (pinfunction "IN_1") (pintype "input"))
      (node (ref "C1") (pin "1") (pinfunction "1_1") (pintype "passive"))
      (node (ref "C42") (pin "1") (pinfunction "1_1") (pintype "passive"))
      (node (ref "C7") (pin "1") (pinfunction "1_1") (pintype "passive"))
      (node (ref "R5") (pin "2") (pinfunction "2_2") (pintype "passive"))
      (node (ref "REG5") (pin "1") (pinfunction "VIN_1") (pintype "input"))
      (node (ref "S5") (pin "1") (pinfunction "O_1") (pintype "passive"))
    )
    (net (code "5") (name "GND") (class "Default")
      (node (ref "9V_1") (pin "2") (pinfunction "GND_1_2") (pintype "power_in"))
      (node (ref "9V_1") (pin "4") (pinfunction "GND_2_4") (pintype "power_in"))
      (node (ref "9V_2") (pin "2") (pinfunction "GND_1_2") (pintype "power_in"))
      (node (ref "9V_2") (pin "4") (pinfunction "GND_2_4") (pintype "power_in"))
      (node (ref "BAT") (pin "2") (pinfunction "S_2") (pintype "passive"))
      (node (ref "C1") (pin "2") (pinfunction "2_2") (pintype "passive"))
      (node (ref "C15") (pin "2") (pinfunction "2_2") (pintype "passive"))
      (node (ref "C16") (pin "2") (pinfunction "2_2") (pintype "passive"))
      (node (ref "C17") (pin "2") (pinfunction "2_2") (pintype "passive"))
      (node (ref "C18") (pin "2") (pinfunction "2_2") (pintype "passive"))
      (node (ref "C19") (pin "2") (pinfunction "2_2") (pintype "passive"))
      (node (ref "C20") (pin "2") (pinfunction "2_2") (pintype "passive"))
      (node (ref "C25") (pin "2") (pinfunction "2_2") (pintype "passive"))
      (node (ref "C27") (pin "2") (pinfunction "2_2") (pintype "passive"))
      (node (ref "C29") (pin "2") (pinfunction "2_2") (pintype "passive"))
      (node (ref "C3") (pin "2") (pinfunction "2_2") (pintype "passive"))
      (node (ref "C30") (pin "2") (pinfunction "2_2") (pintype "passive"))
      (node (ref "C31") (pin "2") (pinfunction "2_2") (pintype "passive"))
      (node (ref "C32") (pin "2") (pinfunction "2_2") (pintype "passive"))
      (node (ref "C34") (pin "2") (pinfunction "2_2") (pintype "passive"))
      (node (ref "C37") (pin "1") (pinfunction "1_1") (pintype "passive"))
      (node (ref "C38") (pin "2") (pinfunction "2_2") (pintype "passive"))
      (node (ref "C4") (pin "2") (pinfunction "2_2") (pintype "passive"))
      (node (ref "C41") (pin "2") (pinfunction "2_2") (pintype "passive"))
      (node (ref "C42") (pin "2") (pinfunction "2_2") (pintype "passive"))
      (node (ref "C43") (pin "2") (pinfunction "2_2") (pintype "passive"))
      (node (ref "C44") (pin "2") (pinfunction "2_2") (pintype "passive"))
      (node (ref "C6") (pin "2") (pinfunction "2_2") (pintype "passive"))
      (node (ref "C7") (pin "2") (pinfunction "2_2") (pintype "passive"))
      (node (ref "C8") (pin "-") (pinfunction "-_-") (pintype "passive"))
      (node (ref "C9") (pin "-") (pinfunction "-_-") (pintype "passive"))
      (node (ref "D4") (pin "A") (pinfunction "A_A") (pintype "passive"))
      (node (ref "D5") (pin "A") (pinfunction "A_A") (pintype "passive"))
      (node (ref "DAC") (pin "7") (pinfunction "GND_7") (pintype "power_in"))
      (node (ref "IC1") (pin "18") (pinfunction "GND1_18") (pintype "power_in"))
      (node (ref "IC1") (pin "28") (pinfunction "GND_28") (pintype "power_in"))
      (node (ref "IC1") (pin "39") (pinfunction "GND2_39") (pintype "power_in"))
      (node (ref "IC1") (pin "6") (pinfunction "GND_6") (pintype "power_in"))
      (node (ref "J11") (pin "21") (pinfunction "KL_21") (pintype "passive"))
      (node (ref "J11") (pin "22") (pinfunction "KL_22") (pintype "passive"))
      (node (ref "J11") (pin "23") (pinfunction "KL_23") (pintype "passive"))
      (node (ref "J11") (pin "24") (pinfunction "KL_24") (pintype "passive"))
      (node (ref "J2") (pin "1") (pinfunction "1_1") (pintype "passive"))
      (node (ref "J3") (pin "1") (pinfunction "1_1") (pintype "passive"))
      (node (ref "J4") (pin "1") (pinfunction "1_1") (pintype "passive"))
      (node (ref "J5") (pin "1") (pinfunction "1_1") (pintype "passive"))
      (node (ref "J8") (pin "GND@1") (pinfunction "GNDBREAK_GND@1") (pintype "bidirectional"))
      (node (ref "J8") (pin "GND@2") (pinfunction "GND_GND@2") (pintype "bidirectional"))
      (node (ref "J9") (pin "4") (pinfunction "4_4") (pintype "passive"))
      (node (ref "JP1") (pin "6") (pinfunction "S_6") (pintype "passive"))
      (node (ref "R10") (pin "1") (pinfunction "1_1") (pintype "passive"))
      (node (ref "R19") (pin "1") (pinfunction "1_1") (pintype "passive"))
      (node (ref "R20") (pin "1") (pinfunction "1_1") (pintype "passive"))
      (node (ref "R21") (pin "1") (pinfunction "1_1") (pintype "passive"))
      (node (ref "R22") (pin "1") (pinfunction "1_1") (pintype "passive"))
      (node (ref "R24") (pin "2") (pinfunction "2_2") (pintype "passive"))
      (node (ref "R27") (pin "2") (pinfunction "2_2") (pintype "passive"))
      (node (ref "R28") (pin "2") (pinfunction "2_2") (pintype "passive"))
      (node (ref "R29") (pin "2") (pinfunction "2_2") (pintype "passive"))
      (node (ref "R30") (pin "1") (pinfunction "1_1") (pintype "passive"))
      (node (ref "R33") (pin "1") (pinfunction "1_1") (pintype "passive"))
      (node (ref "R35") (pin "1") (pinfunction "1_1") (pintype "passive"))
      (node (ref "R37") (pin "1") (pinfunction "1_1") (pintype "passive"))
      (node (ref "R4") (pin "1") (pinfunction "1_1") (pintype "passive"))
      (node (ref "R40") (pin "1") (pinfunction "1_1") (pintype "passive"))
      (node (ref "R44") (pin "1") (pinfunction "1_1") (pintype "passive"))
      (node (ref "R46") (pin "1") (pinfunction "1_1") (pintype "passive"))
      (node (ref "R48") (pin "1") (pinfunction "1_1") (pintype "passive"))
      (node (ref "R51") (pin "1") (pinfunction "1_1") (pintype "passive"))
      (node (ref "R54") (pin "1") (pinfunction "1_1") (pintype "passive"))
      (node (ref "R55") (pin "1") (pinfunction "1_1") (pintype "passive"))
      (node (ref "R58") (pin "1") (pinfunction "1_1") (pintype "passive"))
      (node (ref "R6") (pin "1") (pinfunction "1_1") (pintype "passive"))
      (node (ref "REG5") (pin "2") (pinfunction "GND_2") (pintype "power_in"))
      (node (ref "S5") (pin "B") (pinfunction "B_B") (pintype "passive"))
      (node (ref "S5") (pin "B1") (pinfunction "B1_B1") (pintype "passive"))
      (node (ref "U10") (pin "4") (pinfunction "V-_4") (pintype "power_in"))
      (node (ref "U2") (pin "11") (pinfunction "V-_11") (pintype "power_in"))
      (node (ref "U4") (pin "4") (pinfunction "V-_4") (pintype "power_in"))
      (node (ref "U4") (pin "5") (pinfunction "+IN_5") (pintype "input"))
      (node (ref "U9") (pin "15") (pinfunction "GND_15") (pintype "power_in"))
    )
    (net (code "6") (name "Net-(C20-Pad1)") (class "Default")
      (node (ref "C20") (pin "1") (pinfunction "1_1") (pintype "passive"))
      (node (ref "R7") (pin "2") (pinfunction "2_2") (pintype "passive"))
      (node (ref "R8") (pin "1") (pinfunction "1_1") (pintype "passive"))
    )
    (net (code "7") (name "Net-(C21-Pad1)") (class "Default")
      (node (ref "C21") (pin "1") (pinfunction "1_1") (pintype "passive"))
      (node (ref "J4") (pin "2") (pinfunction "2_2") (pintype "passive"))
      (node (ref "J4") (pin "5") (pinfunction "5_5") (pintype "passive"))
      (node (ref "R7") (pin "1") (pinfunction "1_1") (pintype "passive"))
    )
    (net (code "8") (name "Net-(C22-Pad2)") (class "Default")
      (node (ref "C22") (pin "2") (pinfunction "2_2") (pintype "passive"))
      (node (ref "R13") (pin "2") (pinfunction "2_2") (pintype "passive"))
    )
    (net (code "9") (name "Net-(C23-Pad1)") (class "Default")
      (node (ref "C23") (pin "1") (pinfunction "1_1") (pintype "passive"))
      (node (ref "R14") (pin "2") (pinfunction "2_2") (pintype "passive"))
    )
    (net (code "10") (name "Net-(C24-Pad1)") (class "Default")
      (node (ref "C24") (pin "1") (pinfunction "1_1") (pintype "passive"))
      (node (ref "R15") (pin "2") (pinfunction "2_2") (pintype "passive"))
    )
    (net (code "11") (name "Net-(C43-Pad1)") (class "Default")
      (node (ref "C43") (pin "1") (pinfunction "1_1") (pintype "passive"))
      (node (ref "R11") (pin "1") (pinfunction "1_1") (pintype "passive"))
    )
    (net (code "12") (name "Net-(DAC-VOUT_A)") (class "Default")
      (node (ref "DAC") (pin "8") (pinfunction "VOUT_A_8") (pintype "output"))
      (node (ref "R42") (pin "1") (pinfunction "1_1") (pintype "passive"))
    )
    (net (code "13") (name "Net-(DAC-VOUT_B)") (class "Default")
      (node (ref "DAC") (pin "5") (pinfunction "VOUT_B_5") (pintype "output"))
      (node (ref "R31") (pin "1") (pinfunction "1_1") (pintype "passive"))
    )
    (net (code "14") (name "Net-(IC1-(ADC2)PA2)") (class "Default")
      (node (ref "D5") (pin "C") (pinfunction "C_C") (pintype "passive"))
      (node (ref "IC1") (pin "35") (pinfunction "(ADC2)PA2_35") (pintype "bidirectional"))
      (node (ref "R3") (pin "1") (pinfunction "1_1") (pintype "passive"))
      (node (ref "R4") (pin "2") (pinfunction "2_2") (pintype "passive"))
    )
    (net (code "15") (name "Net-(IC1-(ADC3)PA3)") (class "Default")
      (node (ref "IC1") (pin "34") (pinfunction "(ADC3)PA3_34") (pintype "bidirectional"))
      (node (ref "R5") (pin "1") (pinfunction "1_1") (pintype "passive"))
      (node (ref "R6") (pin "2") (pinfunction "2_2") (pintype "passive"))
    )
    (net (code "16") (name "Net-(IC1-XTAL1)") (class "Default")
      (node (ref "C15") (pin "1") (pinfunction "1_1") (pintype "passive"))
      (node (ref "IC1") (pin "8") (pinfunction "XTAL1_8") (pintype "bidirectional"))
      (node (ref "Y2") (pin "1") (pinfunction "1_1") (pintype "passive"))
    )
    (net (code "17") (name "Net-(IC1-XTAL2)") (class "Default")
      (node (ref "C16") (pin "1") (pinfunction "1_1") (pintype "passive"))
      (node (ref "IC1") (pin "7") (pinfunction "XTAL2_7") (pintype "bidirectional"))
      (node (ref "Y2") (pin "2") (pinfunction "2_2") (pintype "passive"))
    )
    (net (code "18") (name "Net-(J2-Pad2)") (class "Default")
      (node (ref "J2") (pin "2") (pinfunction "2_2") (pintype "passive"))
      (node (ref "R18") (pin "1") (pinfunction "1_1") (pintype "passive"))
      (node (ref "R19") (pin "2") (pinfunction "2_2") (pintype "passive"))
    )
    (net (code "19") (name "Net-(J2-Pad5)") (class "Default")
      (node (ref "J2") (pin "5") (pinfunction "5_5") (pintype "passive"))
      (node (ref "R62") (pin "1") (pinfunction "1_1") (pintype "passive"))
    )
    (net (code "20") (name "Net-(J5-Pad2)") (class "Default")
      (node (ref "J5") (pin "2") (pinfunction "2_2") (pintype "passive"))
      (node (ref "R15") (pin "1") (pinfunction "1_1") (pintype "passive"))
    )
    (net (code "21") (name "Net-(J5-Pad5)") (class "Default")
      (node (ref "J5") (pin "5") (pinfunction "5_5") (pintype "passive"))
      (node (ref "R14") (pin "1") (pinfunction "1_1") (pintype "passive"))
    )
    (net (code "22") (name "Net-(J6-Pad1)") (class "Default")
      (node (ref "J6") (pin "1") (pinfunction "1_1") (pintype "passive"))
      (node (ref "TR1") (pin "1") (pinfunction "1_1") (pintype "passive"))
    )
    (net (code "23") (name "Net-(J6-Pad5)") (class "Default")
      (node (ref "J6") (pin "5") (pinfunction "5_5") (pintype "passive"))
      (node (ref "TR1") (pin "3") (pinfunction "3_3") (pintype "passive"))
    )
    (net (code "24") (name "Net-(J7-Pad1)") (class "Default")
      (node (ref "J7") (pin "1") (pinfunction "1_1") (pintype "passive"))
      (node (ref "TR2") (pin "1") (pinfunction "1_1") (pintype "passive"))
    )
    (net (code "25") (name "Net-(J7-Pad5)") (class "Default")
      (node (ref "J7") (pin "5") (pinfunction "5_5") (pintype "passive"))
      (node (ref "TR2") (pin "3") (pinfunction "3_3") (pintype "passive"))
    )
    (net (code "26") (name "Net-(J9-Pad2)") (class "Default")
      (node (ref "J9") (pin "2") (pinfunction "2_2") (pintype "passive"))
      (node (ref "R58") (pin "2") (pinfunction "2_2") (pintype "passive"))
      (node (ref "R9") (pin "1") (pinfunction "1_1") (pintype "passive"))
    )
    (net (code "27") (name "Net-(Q1-D-Pad2)") (class "Default")
      (node (ref "Q1") (pin "2") (pinfunction "D_2") (pintype "passive"))
      (node (ref "Q1") (pin "4") (pinfunction "D_4") (pintype "passive"))
      (node (ref "TR1") (pin "4") (pinfunction "4_4") (pintype "passive"))
    )
    (net (code "28") (name "Net-(Q1-G)") (class "Default")
      (node (ref "Q1") (pin "1") (pinfunction "G_1") (pintype "passive"))
      (node (ref "R38") (pin "2") (pinfunction "2_2") (pintype "passive"))
    )
    (net (code "29") (name "Net-(Q2-D-Pad2)") (class "Default")
      (node (ref "Q2") (pin "2") (pinfunction "D_2") (pintype "passive"))
      (node (ref "Q2") (pin "4") (pinfunction "D_4") (pintype "passive"))
      (node (ref "TR1") (pin "6") (pinfunction "6_6") (pintype "passive"))
    )
    (net (code "30") (name "Net-(Q2-G)") (class "Default")
      (node (ref "Q2") (pin "1") (pinfunction "G_1") (pintype "passive"))
      (node (ref "R41") (pin "2") (pinfunction "2_2") (pintype "passive"))
    )
    (net (code "31") (name "Net-(Q3-D-Pad2)") (class "Default")
      (node (ref "Q3") (pin "2") (pinfunction "D_2") (pintype "passive"))
      (node (ref "Q3") (pin "4") (pinfunction "D_4") (pintype "passive"))
      (node (ref "TR1") (pin "5") (pinfunction "5_5") (pintype "passive"))
    )
    (net (code "32") (name "Net-(Q3-G)") (class "Default")
      (node (ref "C39") (pin "1") (pinfunction "1_1") (pintype "passive"))
      (node (ref "Q3") (pin "1") (pinfunction "G_1") (pintype "passive"))
      (node (ref "R39") (pin "2") (pinfunction "2_2") (pintype "passive"))
    )
    (net (code "33") (name "Net-(Q4-D-Pad2)") (class "Default")
      (node (ref "Q4") (pin "2") (pinfunction "D_2") (pintype "passive"))
      (node (ref "Q4") (pin "4") (pinfunction "D_4") (pintype "passive"))
      (node (ref "TR2") (pin "4") (pinfunction "4_4") (pintype "passive"))
    )
    (net (code "34") (name "Net-(Q4-G)") (class "Default")
      (node (ref "Q4") (pin "1") (pinfunction "G_1") (pintype "passive"))
      (node (ref "R49") (pin "2") (pinfunction "2_2") (pintype "passive"))
    )
    (net (code "35") (name "Net-(Q5-D-Pad2)") (class "Default")
      (node (ref "Q5") (pin "2") (pinfunction "D_2") (pintype "passive"))
      (node (ref "Q5") (pin "4") (pinfunction "D_4") (pintype "passive"))
      (node (ref "TR2") (pin "6") (pinfunction "6_6") (pintype "passive"))
    )
    (net (code "36") (name "Net-(Q5-G)") (class "Default")
      (node (ref "Q5") (pin "1") (pinfunction "G_1") (pintype "passive"))
      (node (ref "R52") (pin "2") (pinfunction "2_2") (pintype "passive"))
    )
    (net (code "37") (name "Net-(Q6-D-Pad2)") (class "Default")
      (node (ref "Q6") (pin "2") (pinfunction "D_2") (pintype "passive"))
      (node (ref "Q6") (pin "4") (pinfunction "D_4") (pintype "passive"))
      (node (ref "TR2") (pin "5") (pinfunction "5_5") (pintype "passive"))
    )
    (net (code "38") (name "Net-(Q6-G)") (class "Default")
      (node (ref "C40") (pin "1") (pinfunction "1_1") (pintype "passive"))
      (node (ref "Q6") (pin "1") (pinfunction "G_1") (pintype "passive"))
      (node (ref "R50") (pin "2") (pinfunction "2_2") (pintype "passive"))
    )
    (net (code "39") (name "Net-(R55-Pad2)") (class "Default")
      (node (ref "R55") (pin "2") (pinfunction "2_2") (pintype "passive"))
      (node (ref "TU") (pin "1") (pinfunction "1_1") (pintype "passive"))
    )
    (net (code "40") (name "Net-(S5-P)") (class "Default")
      (node (ref "D4") (pin "C") (pinfunction "C_C") (pintype "passive"))
      (node (ref "F1") (pin "2") (pinfunction "2_2") (pintype "passive"))
      (node (ref "S5") (pin "2") (pinfunction "P_2") (pintype "passive"))
      (node (ref "S5") (pin "3") (pinfunction "S_3") (pintype "passive"))
    )
    (net (code "41") (name "Net-(U2A-+IN)") (class "Default")
      (node (ref "C28") (pin "2") (pinfunction "2_2") (pintype "passive"))
      (node (ref "R21") (pin "2") (pinfunction "2_2") (pintype "passive"))
      (node (ref "R62") (pin "2") (pinfunction "2_2") (pintype "passive"))
      (node (ref "U2") (pin "3") (pinfunction "+IN_3") (pintype "input"))
    )
    (net (code "42") (name "Net-(U2A--IN)") (class "Default")
      (node (ref "R24") (pin "1") (pinfunction "1_1") (pintype "passive"))
      (node (ref "R25") (pin "1") (pinfunction "1_1") (pintype "passive"))
      (node (ref "U2") (pin "2") (pinfunction "-IN_2") (pintype "input"))
    )
    (net (code "43") (name "Net-(U2A-OUT)") (class "Default")
      (node (ref "D2") (pin "A") (pinfunction "A_A") (pintype "passive"))
      (node (ref "R25") (pin "2") (pinfunction "2_2") (pintype "passive"))
      (node (ref "U2") (pin "1") (pinfunction "OUT_1") (pintype "output"))
      (node (ref "U2") (pin "12") (pinfunction "+IN_12") (pintype "input"))
    )
    (net (code "44") (name "Net-(U2B-+IN)") (class "Default")
      (node (ref "C26") (pin "2") (pinfunction "2_2") (pintype "passive"))
      (node (ref "R20") (pin "2") (pinfunction "2_2") (pintype "passive"))
      (node (ref "U2") (pin "5") (pinfunction "+IN_5") (pintype "input"))
    )
    (net (code "45") (name "Net-(U2B--IN)") (class "Default")
      (node (ref "R22") (pin "2") (pinfunction "2_2") (pintype "passive"))
      (node (ref "R23") (pin "1") (pinfunction "1_1") (pintype "passive"))
      (node (ref "U2") (pin "6") (pinfunction "-IN_6") (pintype "input"))
    )
    (net (code "46") (name "Net-(U2B-OUT)") (class "Default")
      (node (ref "D3") (pin "A") (pinfunction "A_A") (pintype "passive"))
      (node (ref "R23") (pin "2") (pinfunction "2_2") (pintype "passive"))
      (node (ref "U2") (pin "10") (pinfunction "+IN_10") (pintype "input"))
      (node (ref "U2") (pin "7") (pinfunction "OUT_7") (pintype "output"))
    )
    (net (code "47") (name "Net-(U2C--IN)") (class "Default")
      (node (ref "R26") (pin "1") (pinfunction "1_1") (pintype "passive"))
      (node (ref "R27") (pin "1") (pinfunction "1_1") (pintype "passive"))
      (node (ref "U2") (pin "13") (pinfunction "-IN_13") (pintype "input"))
      (node (ref "U2") (pin "9") (pinfunction "-IN_9") (pintype "input"))
    )
    (net (code "48") (name "Net-(U4A-+IN)") (class "Default")
      (node (ref "C21") (pin "2") (pinfunction "2_2") (pintype "passive"))
      (node (ref "R10") (pin "2") (pinfunction "2_2") (pintype "passive"))
      (node (ref "R61") (pin "1") (pinfunction "1_1") (pintype "passive"))
      (node (ref "U4") (pin "3") (pinfunction "+IN_3") (pintype "input"))
    )
    (net (code "49") (name "Net-(U4A--IN)") (class "Default")
      (node (ref "R11") (pin "2") (pinfunction "2_2") (pintype "passive"))
      (node (ref "R12") (pin "1") (pinfunction "1_1") (pintype "passive"))
      (node (ref "U4") (pin "2") (pinfunction "-IN_2") (pintype "input"))
    )
    (net (code "50") (name "Net-(U4A-OUT)") (class "Default")
      (node (ref "R12") (pin "2") (pinfunction "2_2") (pintype "passive"))
      (node (ref "R13") (pin "1") (pinfunction "1_1") (pintype "passive"))
      (node (ref "U4") (pin "1") (pinfunction "OUT_1") (pintype "output"))
      (node (ref "U4") (pin "6") (pinfunction "-IN_6") (pintype "input"))
    )
    (net (code "51") (name "Net-(U9A-C1+)") (class "Default")
      (node (ref "C35") (pin "1") (pinfunction "1_1") (pintype "passive"))
      (node (ref "U9") (pin "1") (pinfunction "C1+_1") (pintype "bidirectional"))
    )
    (net (code "52") (name "Net-(U9A-C1-)") (class "Default")
      (node (ref "C35") (pin "2") (pinfunction "2_2") (pintype "passive"))
      (node (ref "U9") (pin "3") (pinfunction "C1-_3") (pintype "bidirectional"))
    )
    (net (code "53") (name "Net-(U9A-C2+)") (class "Default")
      (node (ref "C36") (pin "1") (pinfunction "1_1") (pintype "passive"))
      (node (ref "U9") (pin "4") (pinfunction "C2+_4") (pintype "bidirectional"))
    )
    (net (code "54") (name "Net-(U9A-C2-)") (class "Default")
      (node (ref "C36") (pin "2") (pinfunction "2_2") (pintype "passive"))
      (node (ref "U9") (pin "5") (pinfunction "C2-_5") (pintype "bidirectional"))
    )
    (net (code "55") (name "Net-(U9A-R1IN)") (class "Default")
      (node (ref "J3") (pin "2") (pinfunction "2_2") (pintype "passive"))
      (node (ref "U9") (pin "13") (pinfunction "R1IN_13") (pintype "input"))
    )
    (net (code "56") (name "Net-(U9A-R2IN)") (class "Default")
      (node (ref "J3") (pin "4") (pinfunction "4_4") (pintype "passive"))
      (node (ref "U9") (pin "8") (pinfunction "R2IN_8") (pintype "input"))
    )
    (net (code "57") (name "Net-(U9A-R2OUT)") (class "Default")
      (node (ref "R9") (pin "2") (pinfunction "2_2") (pintype "passive"))
      (node (ref "U9") (pin "9") (pinfunction "R2OUT_9") (pintype "output"))
    )
    (net (code "58") (name "Net-(U9A-T1OUT)") (class "Default")
      (node (ref "J3") (pin "5") (pinfunction "5_5") (pintype "passive"))
      (node (ref "U9") (pin "14") (pinfunction "T1OUT_14") (pintype "output"))
    )
    (net (code "59") (name "Net-(U9A-T2IN)") (class "Default")
      (node (ref "J9") (pin "3") (pinfunction "3_3") (pintype "passive"))
      (node (ref "U9") (pin "10") (pinfunction "T2IN_10") (pintype "input"))
    )
    (net (code "60") (name "Net-(U9A-T2OUT)") (class "Default")
      (node (ref "J3") (pin "3") (pinfunction "3_3") (pintype "passive"))
      (node (ref "U9") (pin "7") (pinfunction "T2OUT_7") (pintype "output"))
    )
    (net (code "61") (name "Net-(U9A-V+)") (class "Default")
      (node (ref "C33") (pin "2") (pinfunction "2_2") (pintype "passive"))
      (node (ref "U9") (pin "2") (pinfunction "V+_2") (pintype "bidirectional"))
    )
    (net (code "62") (name "Net-(U9A-V-)") (class "Default")
      (node (ref "C34") (pin "1") (pinfunction "1_1") (pintype "passive"))
      (node (ref "U9") (pin "6") (pinfunction "V-_6") (pintype "bidirectional"))
    )
    (net (code "63") (name "Net-(U10A-+IN)") (class "Default")
      (node (ref "R31") (pin "2") (pinfunction "2_2") (pintype "passive"))
      (node (ref "R32") (pin "1") (pinfunction "1_1") (pintype "passive"))
      (node (ref "R33") (pin "2") (pinfunction "2_2") (pintype "passive"))
      (node (ref "U10") (pin "3") (pinfunction "+IN_3") (pintype "input"))
    )
    (net (code "64") (name "Net-(U10A--IN)") (class "Default")
      (node (ref "R34") (pin "1") (pinfunction "1_1") (pintype "passive"))
      (node (ref "R35") (pin "2") (pinfunction "2_2") (pintype "passive"))
      (node (ref "R36") (pin "1") (pinfunction "1_1") (pintype "passive"))
      (node (ref "U10") (pin "2") (pinfunction "-IN_2") (pintype "input"))
    )
    (net (code "65") (name "Net-(U10A-OUT)") (class "Default")
      (node (ref "R36") (pin "2") (pinfunction "2_2") (pintype "passive"))
      (node (ref "R39") (pin "1") (pinfunction "1_1") (pintype "passive"))
      (node (ref "U10") (pin "1") (pinfunction "OUT_1") (pintype "output"))
    )
    (net (code "66") (name "Net-(U10B-+IN)") (class "Default")
      (node (ref "R42") (pin "2") (pinfunction "2_2") (pintype "passive"))
      (node (ref "R43") (pin "1") (pinfunction "1_1") (pintype "passive"))
      (node (ref "R44") (pin "2") (pinfunction "2_2") (pintype "passive"))
      (node (ref "U10") (pin "5") (pinfunction "+IN_5") (pintype "input"))
    )
    (net (code "67") (name "Net-(U10B--IN)") (class "Default")
      (node (ref "R45") (pin "1") (pinfunction "1_1") (pintype "passive"))
      (node (ref "R46") (pin "2") (pinfunction "2_2") (pintype "passive"))
      (node (ref "R47") (pin "1") (pinfunction "1_1") (pintype "passive"))
      (node (ref "U10") (pin "6") (pinfunction "-IN_6") (pintype "input"))
    )
    (net (code "68") (name "Net-(U10B-OUT)") (class "Default")
      (node (ref "R47") (pin "2") (pinfunction "2_2") (pintype "passive"))
      (node (ref "R50") (pin "1") (pinfunction "1_1") (pintype "passive"))
      (node (ref "U10") (pin "7") (pinfunction "OUT_7") (pintype "output"))
    )
    (net (code "69") (name "PA0") (class "Default")
      (node (ref "IC1") (pin "37") (pinfunction "(ADC0)PA0_37") (pintype "bidirectional"))
      (node (ref "Q1") (pin "3") (pinfunction "S_3") (pintype "passive"))
      (node (ref "Q2") (pin "3") (pinfunction "S_3") (pintype "passive"))
      (node (ref "Q4") (pin "3") (pinfunction "S_3") (pintype "passive"))
      (node (ref "Q5") (pin "3") (pinfunction "S_3") (pintype "passive"))
      (node (ref "R30") (pin "2") (pinfunction "2_2") (pintype "passive"))
      (node (ref "R54") (pin "2") (pinfunction "2_2") (pintype "passive"))
      (node (ref "TU") (pin "2") (pinfunction "2_2") (pintype "passive"))
    )
    (net (code "70") (name "PA1") (class "Default")
      (node (ref "C25") (pin "1") (pinfunction "1_1") (pintype "passive"))
      (node (ref "C26") (pin "1") (pinfunction "1_1") (pintype "passive"))
      (node (ref "IC1") (pin "36") (pinfunction "(ADC1)PA1_36") (pintype "bidirectional"))
      (node (ref "J11") (pin "5") (pinfunction "KL_5") (pintype "passive"))
    )
    (net (code "71") (name "PA4") (class "Default")
      (node (ref "IC1") (pin "33") (pinfunction "(ADC4)PA4_33") (pintype "bidirectional"))
      (node (ref "J11") (pin "9") (pinfunction "KL_9") (pintype "passive"))
    )
    (net (code "72") (name "PA5") (class "Default")
      (node (ref "IC1") (pin "32") (pinfunction "(ADC5)PA5_32") (pintype "bidirectional"))
      (node (ref "J11") (pin "11") (pinfunction "KL_11") (pintype "passive"))
    )
    (net (code "73") (name "PA6") (class "Default")
      (node (ref "C31") (pin "1") (pinfunction "1_1") (pintype "passive"))
      (node (ref "D2") (pin "C") (pinfunction "C_C") (pintype "passive"))
      (node (ref "IC1") (pin "31") (pinfunction "(ADC6)PA6_31") (pintype "bidirectional"))
      (node (ref "R29") (pin "1") (pinfunction "1_1") (pintype "passive"))
    )
    (net (code "74") (name "PA7") (class "Default")
      (node (ref "C30") (pin "1") (pinfunction "1_1") (pintype "passive"))
      (node (ref "D3") (pin "C") (pinfunction "C_C") (pintype "passive"))
      (node (ref "IC1") (pin "30") (pinfunction "(ADC7)PA7_30") (pintype "bidirectional"))
      (node (ref "R28") (pin "1") (pinfunction "1_1") (pintype "passive"))
    )
    (net (code "75") (name "PB0") (class "Default")
      (node (ref "IC1") (pin "40") (pinfunction "(T0/XCK)PB0_40") (pintype "bidirectional"))
      (node (ref "R48") (pin "2") (pinfunction "2_2") (pintype "passive"))
      (node (ref "R49") (pin "1") (pinfunction "1_1") (pintype "passive"))
    )
    (net (code "76") (name "PB1") (class "Default")
      (node (ref "IC1") (pin "41") (pinfunction "(T1)PB1_41") (pintype "bidirectional"))
      (node (ref "R51") (pin "2") (pinfunction "2_2") (pintype "passive"))
      (node (ref "R52") (pin "1") (pinfunction "1_1") (pintype "passive"))
    )
    (net (code "77") (name "PB2") (class "Default")
      (node (ref "IC1") (pin "42") (pinfunction "(AIN0/INT2)PB2_42") (pintype "bidirectional"))
      (node (ref "R37") (pin "2") (pinfunction "2_2") (pintype "passive"))
      (node (ref "R38") (pin "1") (pinfunction "1_1") (pintype "passive"))
    )
    (net (code "78") (name "PB3") (class "Default")
      (node (ref "IC1") (pin "43") (pinfunction "(AIN1/OC0)PB3_43") (pintype "bidirectional"))
      (node (ref "R40") (pin "2") (pinfunction "2_2") (pintype "passive"))
      (node (ref "R41") (pin "1") (pinfunction "1_1") (pintype "passive"))
    )
    (net (code "79") (name "PB5") (class "Default")
      (node (ref "DAC") (pin "3") (pinfunction "D_IN_3") (pintype "input"))
      (node (ref "IC1") (pin "1") (pinfunction "(MOSI)PB5_1") (pintype "bidirectional"))
      (node (ref "JP1") (pin "4") (pinfunction "S_4") (pintype "passive"))
    )
    (net (code "80") (name "PB6") (class "Default")
      (node (ref "IC1") (pin "2") (pinfunction "(MISO)PB6_2") (pintype "bidirectional"))
      (node (ref "JP1") (pin "1") (pinfunction "S_1") (pintype "passive"))
    )
    (net (code "81") (name "PB7") (class "Default")
      (node (ref "DAC") (pin "2") (pinfunction "SCK_2") (pintype "input"))
      (node (ref "IC1") (pin "3") (pinfunction "(SCK)PB7_3") (pintype "bidirectional"))
      (node (ref "JP1") (pin "3") (pinfunction "S_3") (pintype "passive"))
    )
    (net (code "82") (name "PC0") (class "Default")
      (node (ref "IC1") (pin "19") (pinfunction "PC0(SCL)_19") (pintype "bidirectional"))
      (node (ref "J11") (pin "2") (pinfunction "KL_2") (pintype "passive"))
    )
    (net (code "83") (name "PC1") (class "Default")
      (node (ref "IC1") (pin "20") (pinfunction "PC1(SDA)_20") (pintype "bidirectional"))
      (node (ref "J11") (pin "4") (pinfunction "KL_4") (pintype "passive"))
    )
    (net (code "84") (name "PC2") (class "Default")
      (node (ref "IC1") (pin "21") (pinfunction "(TCK)PC2_21") (pintype "bidirectional"))
      (node (ref "J11") (pin "6") (pinfunction "KL_6") (pintype "passive"))
    )
    (net (code "85") (name "PC3") (class "Default")
      (node (ref "IC1") (pin "22") (pinfunction "(TMS)PC3_22") (pintype "bidirectional"))
      (node (ref "J11") (pin "8") (pinfunction "KL_8") (pintype "passive"))
    )
    (net (code "86") (name "PC4") (class "Default")
      (node (ref "IC1") (pin "23") (pinfunction "(TDO)PC4_23") (pintype "bidirectional"))
      (node (ref "J11") (pin "10") (pinfunction "KL_10") (pintype "passive"))
    )
    (net (code "87") (name "PC5") (class "Default")
      (node (ref "IC1") (pin "24") (pinfunction "(TDI)PC5_24") (pintype "bidirectional"))
      (node (ref "J11") (pin "12") (pinfunction "KL_12") (pintype "passive"))
    )
    (net (code "88") (name "PC6") (class "Default")
      (node (ref "IC1") (pin "25") (pinfunction "(TOSC1)PC6_25") (pintype "bidirectional"))
      (node (ref "J11") (pin "14") (pinfunction "KL_14") (pintype "passive"))
    )
    (net (code "89") (name "PC7") (class "Default")
      (node (ref "IC1") (pin "26") (pinfunction "(TOSC2)PC7_26") (pintype "bidirectional"))
      (node (ref "J11") (pin "16") (pinfunction "KL_16") (pintype "passive"))
    )
    (net (code "90") (name "PD0") (class "Default")
      (node (ref "IC1") (pin "9") (pinfunction "(RXD)PD0_9") (pintype "bidirectional"))
      (node (ref "U9") (pin "12") (pinfunction "R1OUT_12") (pintype "output"))
    )
    (net (code "91") (name "PD1") (class "Default")
      (node (ref "IC1") (pin "10") (pinfunction "(TXD)PD1_10") (pintype "bidirectional"))
      (node (ref "U9") (pin "11") (pinfunction "T1IN_11") (pintype "input"))
    )
    (net (code "92") (name "PD2") (class "Default")
      (node (ref "IC1") (pin "11") (pinfunction "(INT0)PD2_11") (pintype "bidirectional"))
      (node (ref "U2") (pin "14") (pinfunction "OUT_14") (pintype "output"))
    )
    (net (code "93") (name "PD3") (class "Default")
      (node (ref "IC1") (pin "12") (pinfunction "(INT1)PD3_12") (pintype "bidirectional"))
      (node (ref "U2") (pin "8") (pinfunction "OUT_8") (pintype "output"))
    )
    (net (code "94") (name "PD5") (class "Default")
      (node (ref "IC1") (pin "14") (pinfunction "(OC1A)PD5_14") (pintype "bidirectional"))
      (node (ref "J11") (pin "15") (pinfunction "KL_15") (pintype "passive"))
    )
    (net (code "95") (name "PD6") (class "Default")
      (node (ref "IC1") (pin "15") (pinfunction "(ICP)PD6_15") (pintype "bidirectional"))
      (node (ref "J11") (pin "13") (pinfunction "KL_13") (pintype "passive"))
    )
    (net (code "96") (name "PD7") (class "Default")
      (node (ref "IC1") (pin "16") (pinfunction "(OC2)PD7_16") (pintype "bidirectional"))
      (node (ref "J11") (pin "18") (pinfunction "KL_18") (pintype "passive"))
    )
    (net (code "97") (name "RB4") (class "Default")
      (node (ref "C27") (pin "1") (pinfunction "1_1") (pintype "passive"))
      (node (ref "C28") (pin "1") (pinfunction "1_1") (pintype "passive"))
      (node (ref "J11") (pin "7") (pinfunction "KL_7") (pintype "passive"))
    )
    (net (code "98") (name "RB9") (class "Default")
      (node (ref "C22") (pin "1") (pinfunction "1_1") (pintype "passive"))
      (node (ref "C24") (pin "2") (pinfunction "2_2") (pintype "passive"))
      (node (ref "J11") (pin "3") (pinfunction "KL_3") (pintype "passive"))
      (node (ref "R17") (pin "1") (pinfunction "1_1") (pintype "passive"))
    )
    (net (code "99") (name "RB10") (class "Default")
      (node (ref "C23") (pin "2") (pinfunction "2_2") (pintype "passive"))
      (node (ref "J11") (pin "1") (pinfunction "KL_1") (pintype "passive"))
      (node (ref "R16") (pin "1") (pinfunction "1_1") (pintype "passive"))
    )
    (net (code "100") (name "RESET") (class "Default")
      (node (ref "C37") (pin "2") (pinfunction "2_2") (pintype "passive"))
      (node (ref "IC1") (pin "4") (pinfunction "RESET_4") (pintype "input"))
      (node (ref "JP1") (pin "5") (pinfunction "S_5") (pintype "passive"))
      (node (ref "R53") (pin "1") (pinfunction "1_1") (pintype "passive"))
    )
    (net (code "101") (name "STATE") (class "Default")
      (node (ref "J11") (pin "17") (pinfunction "KL_17") (pintype "passive"))
      (node (ref "J9") (pin "1") (pinfunction "1_1") (pintype "passive"))
    )
    (net (code "102") (name "V+") (class "Default")
      (node (ref "BAT") (pin "1") (pinfunction "S_1") (pintype "passive"))
      (node (ref "F1") (pin "1") (pinfunction "1_1") (pintype "passive"))
      (node (ref "J8") (pin "PWR") (pinfunction "PWR_PWR") (pintype "bidirectional"))
      (node (ref "R3") (pin "2") (pinfunction "2_2") (pintype "passive"))
    )
    (net (code "103") (name "unconnected-(IC1-(SS)PB4-Pad44)") (class "Default")
      (node (ref "IC1") (pin "44") (pinfunction "(SS)PB4_44") (pintype "bidirectional"))
    )
    (net (code "104") (name "unconnected-(J2-Pad3)") (class "Default")
      (node (ref "J2") (pin "3") (pinfunction "3_3") (pintype "passive"))
    )
    (net (code "105") (name "unconnected-(J2-Pad4)") (class "Default")
      (node (ref "J2") (pin "4") (pinfunction "4_4") (pintype "passive"))
    )
    (net (code "106") (name "unconnected-(J4-Pad3)") (class "Default")
      (node (ref "J4") (pin "3") (pinfunction "3_3") (pintype "passive"))
    )
    (net (code "107") (name "unconnected-(J4-Pad4)") (class "Default")
      (node (ref "J4") (pin "4") (pinfunction "4_4") (pintype "passive"))
    )
    (net (code "108") (name "unconnected-(J5-Pad3)") (class "Default")
      (node (ref "J5") (pin "3") (pinfunction "3_3") (pintype "passive"))
    )
    (net (code "109") (name "unconnected-(J5-Pad4)") (class "Default")
      (node (ref "J5") (pin "4") (pinfunction "4_4") (pintype "passive"))
    )
    (net (code "110") (name "unconnected-(J6-Pad2)") (class "Default")
      (node (ref "J6") (pin "2") (pinfunction "2_2") (pintype "passive"))
    )
    (net (code "111") (name "unconnected-(J6-Pad3)") (class "Default")
      (node (ref "J6") (pin "3") (pinfunction "3_3") (pintype "passive"))
    )
    (net (code "112") (name "unconnected-(J6-Pad4)") (class "Default")
      (node (ref "J6") (pin "4") (pinfunction "4_4") (pintype "passive"))
    )
    (net (code "113") (name "unconnected-(J7-Pad2)") (class "Default")
      (node (ref "J7") (pin "2") (pinfunction "2_2") (pintype "passive"))
    )
    (net (code "114") (name "unconnected-(J7-Pad3)") (class "Default")
      (node (ref "J7") (pin "3") (pinfunction "3_3") (pintype "passive"))
    )
    (net (code "115") (name "unconnected-(J7-Pad4)") (class "Default")
      (node (ref "J7") (pin "4") (pinfunction "4_4") (pintype "passive"))
    )
    (net (code "116") (name "unconnected-(J9-Pad6)") (class "Default")
      (node (ref "J9") (pin "6") (pinfunction "6_6") (pintype "passive"))
    )
    (net (code "117") (name "unconnected-(TR1-Pad2)") (class "Default")
      (node (ref "TR1") (pin "2") (pinfunction "2_2") (pintype "passive"))
    )
    (net (code "118") (name "unconnected-(TR2-Pad2)") (class "Default")
      (node (ref "TR2") (pin "2") (pinfunction "2_2") (pintype "passive"))
    )
    (net (code "119") (name "unconnected-(U4B-OUT-Pad7)") (class "Default")
      (node (ref "U4") (pin "7") (pinfunction "OUT_7") (pintype "output"))
    )
    (net (code "120") (name "~{CS}") (class "Default")
      (node (ref "DAC") (pin "1") (pinfunction "CS/LD_1") (pintype "input"))
      (node (ref "IC1") (pin "13") (pinfunction "(OC1B)PD4_13") (pintype "bidirectional"))
    )
  )
)
